# ADCS_Motherboard.net
KiCad netlist of a schematic drawn in EAGLE
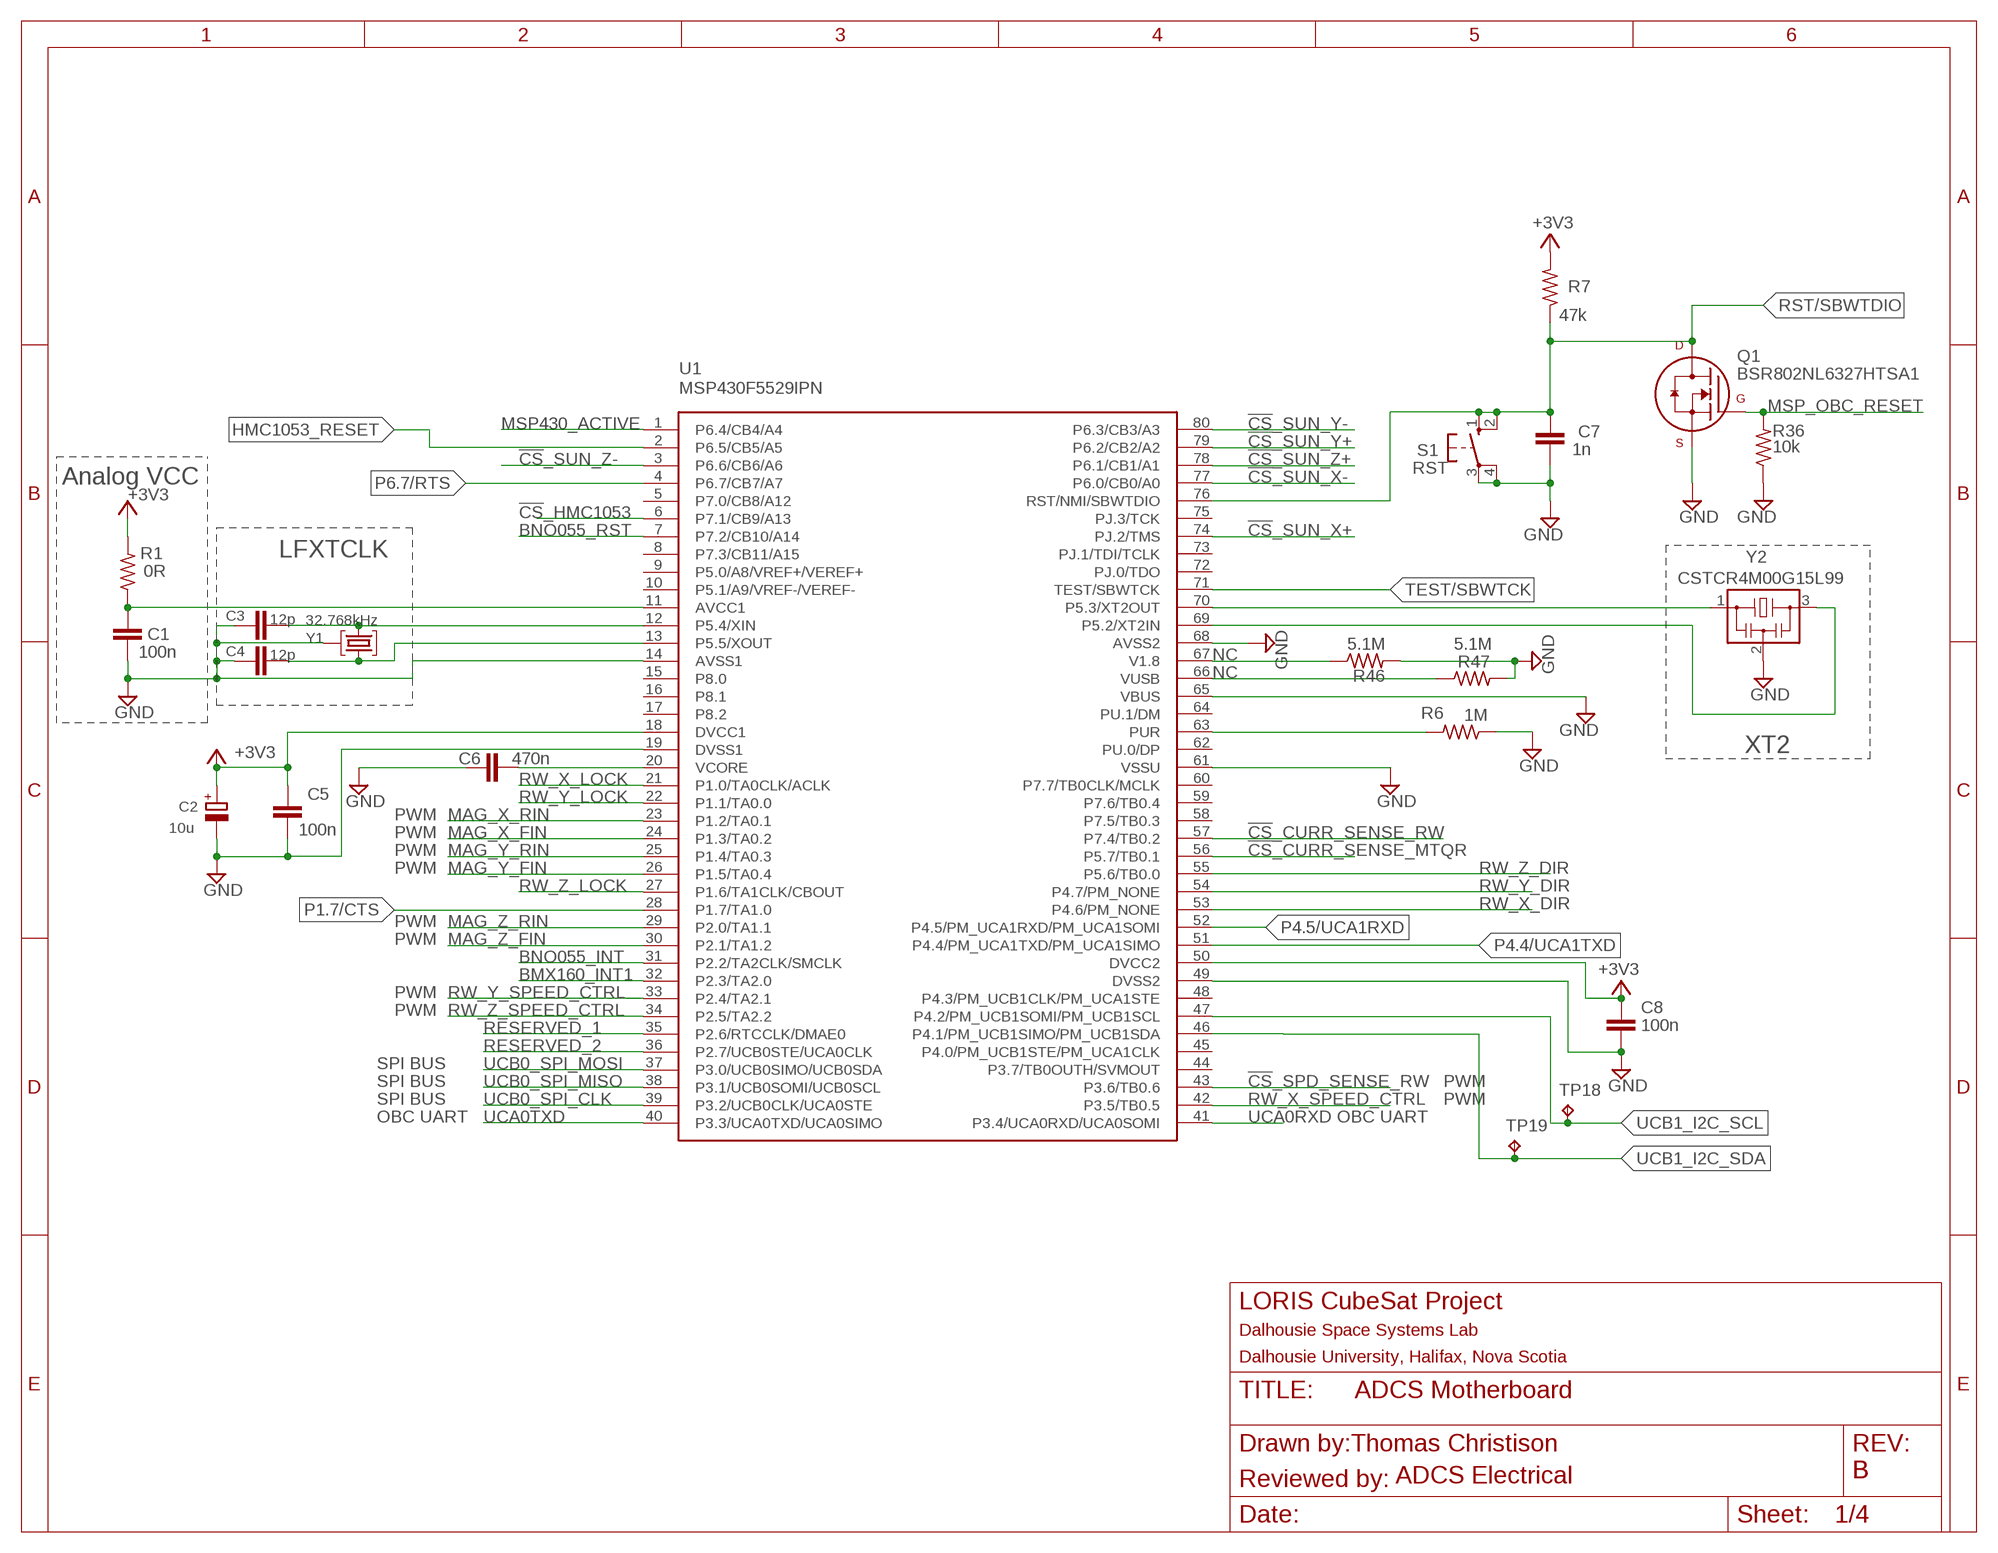
[diagram p0: schematic, sheet 1]
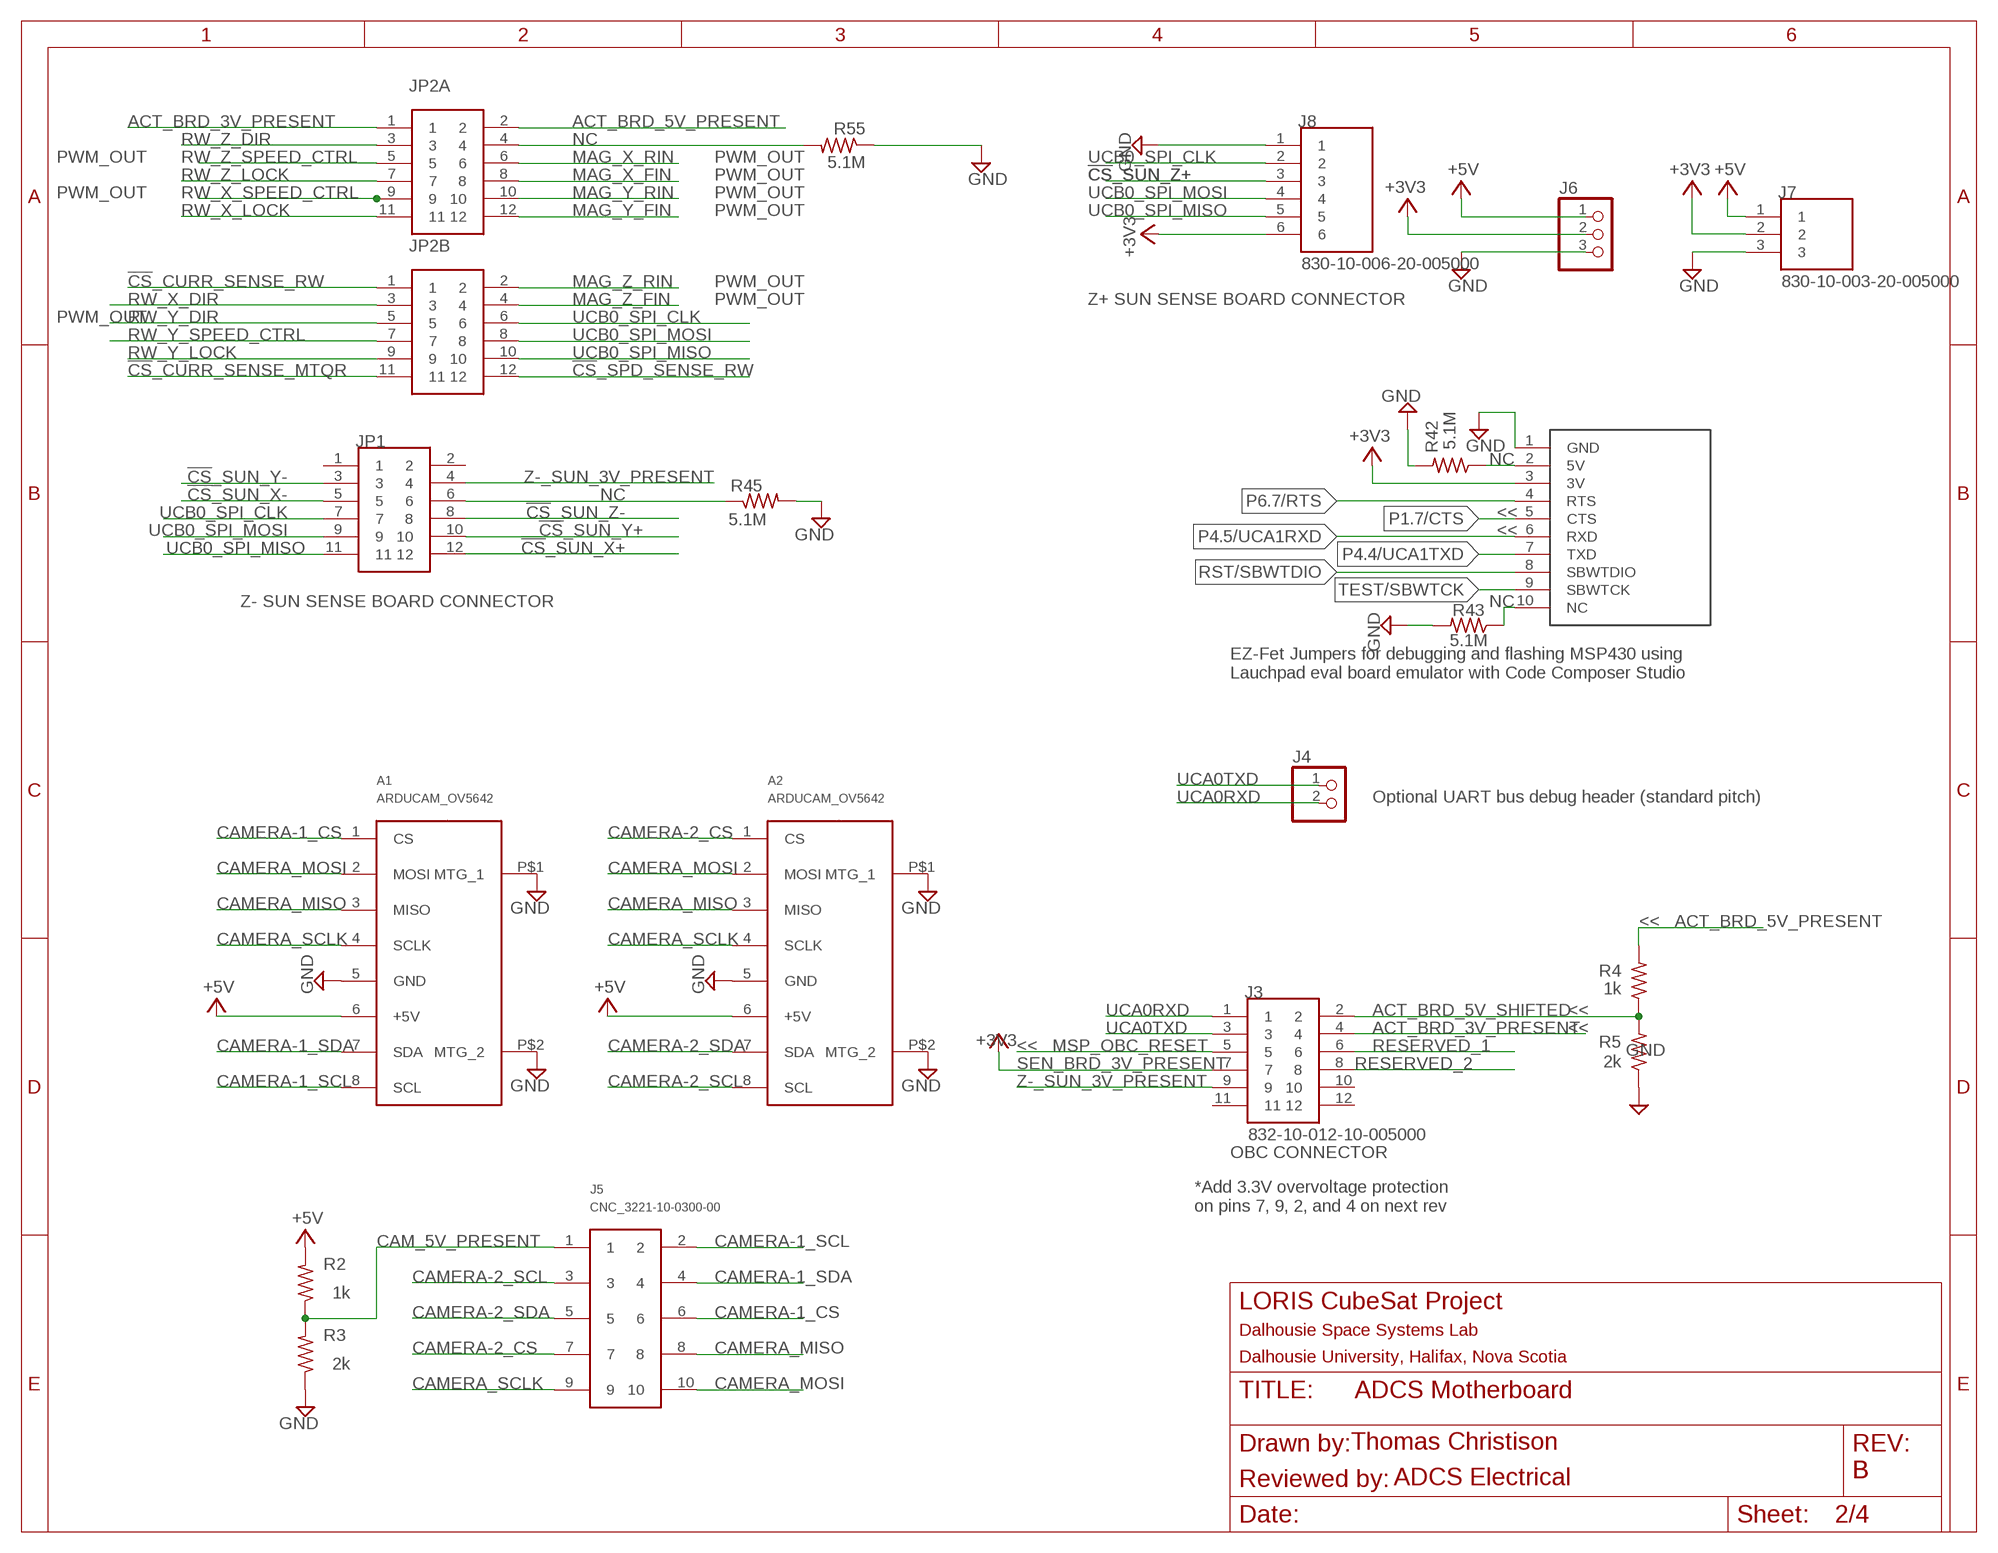
[diagram p1: schematic, sheet 2]
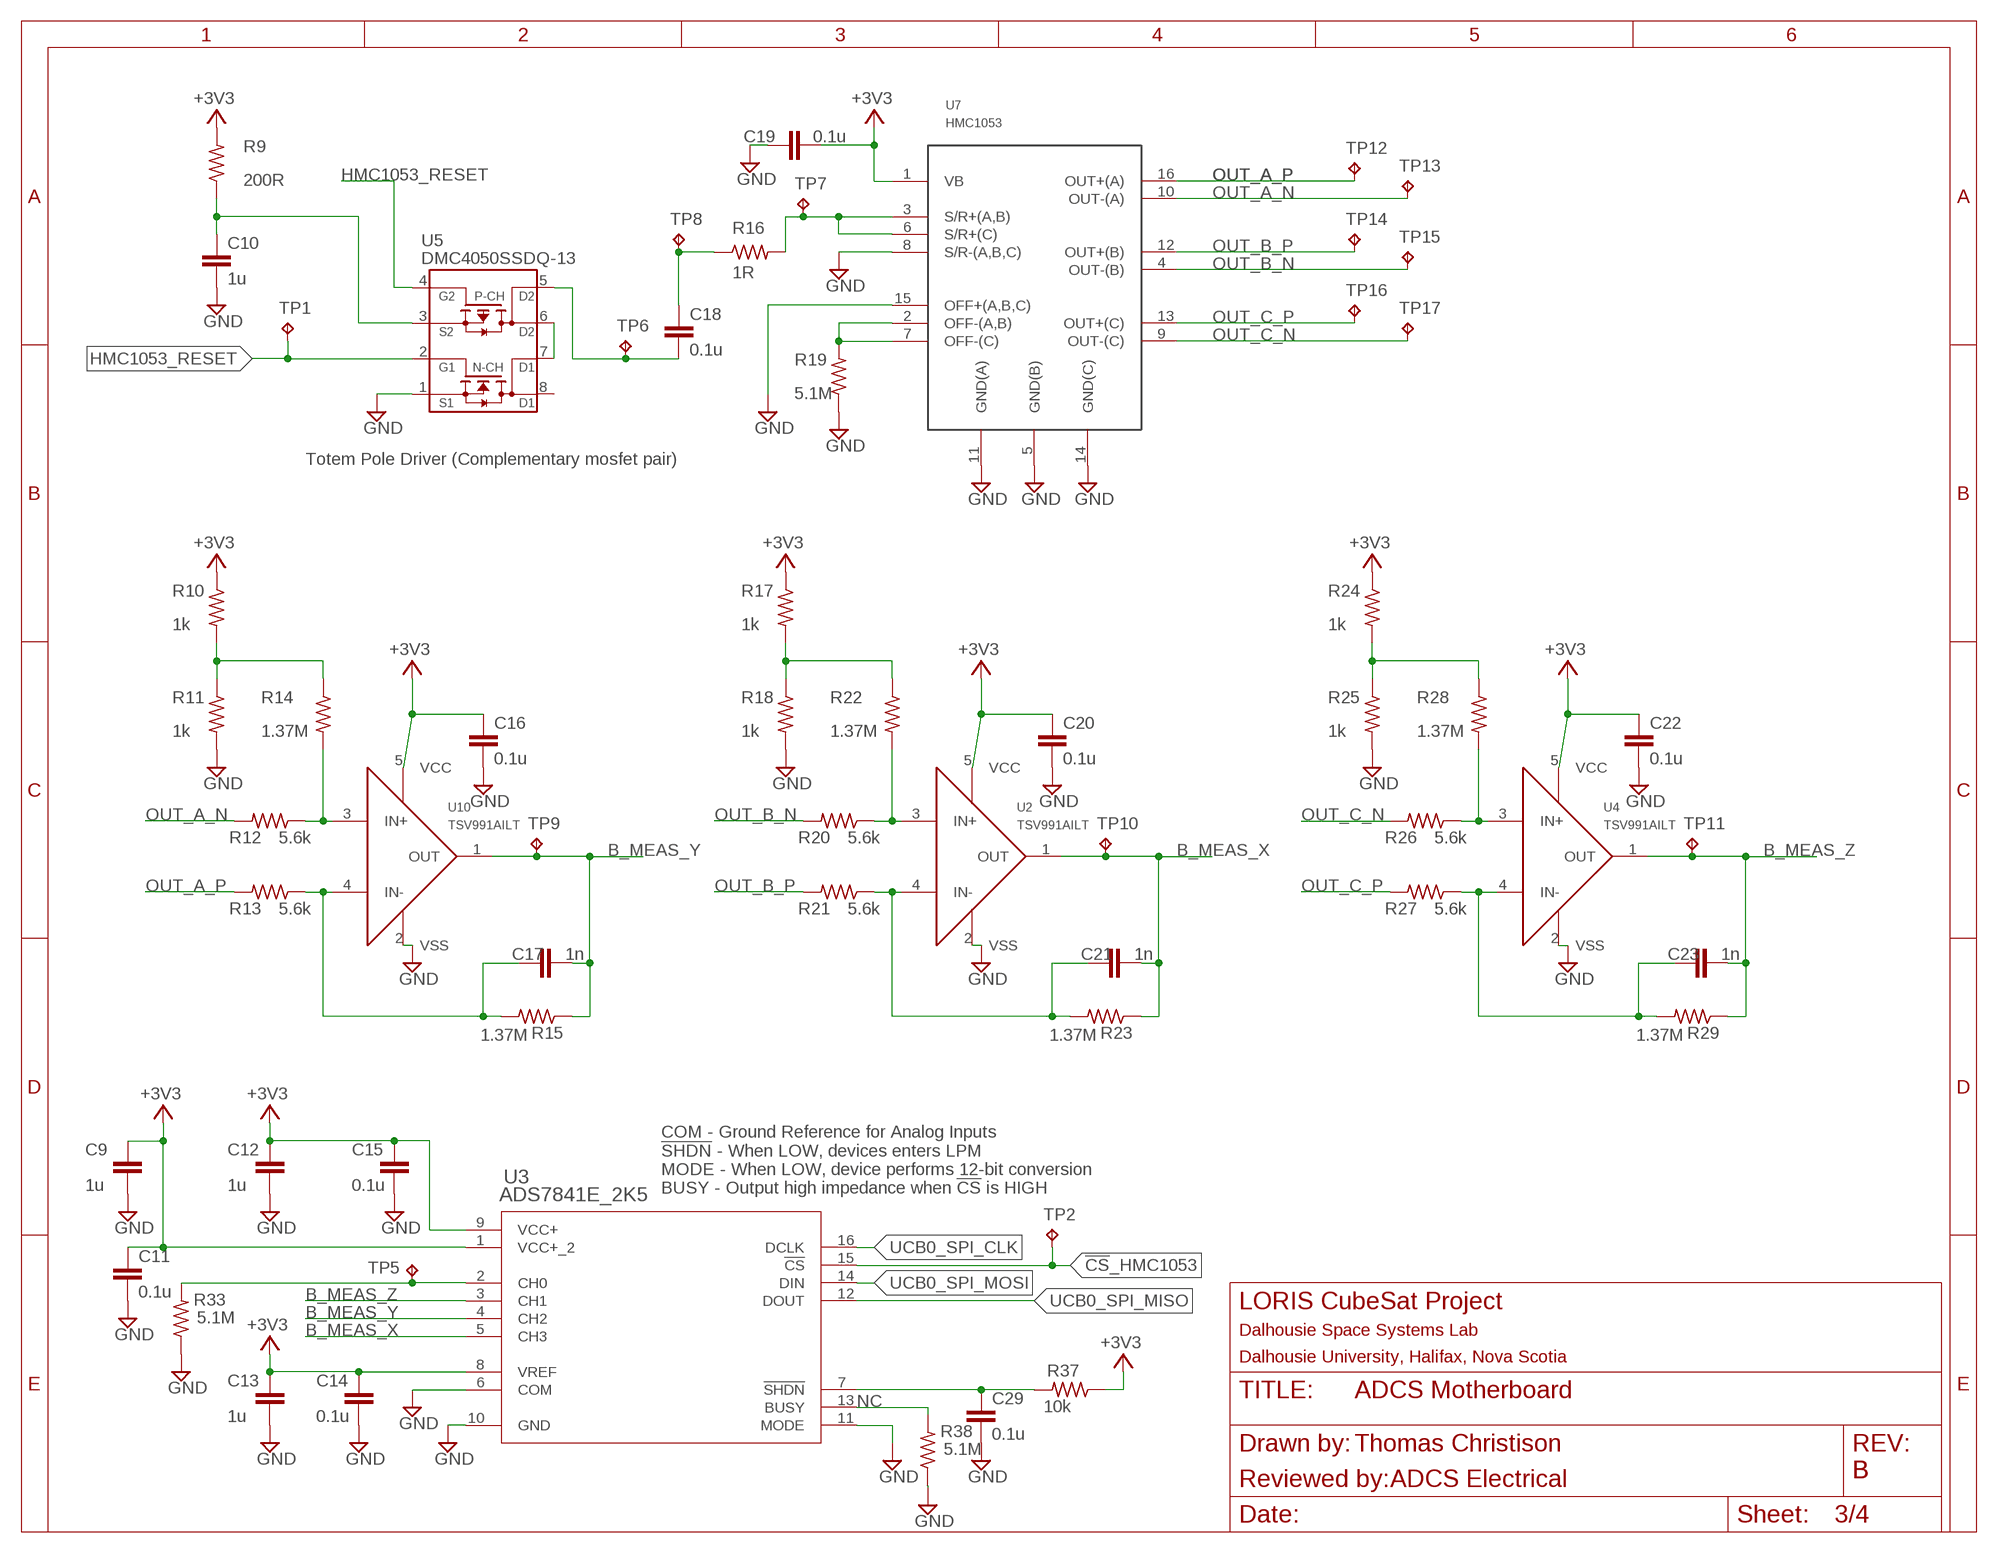
[diagram p2: schematic, sheet 3]
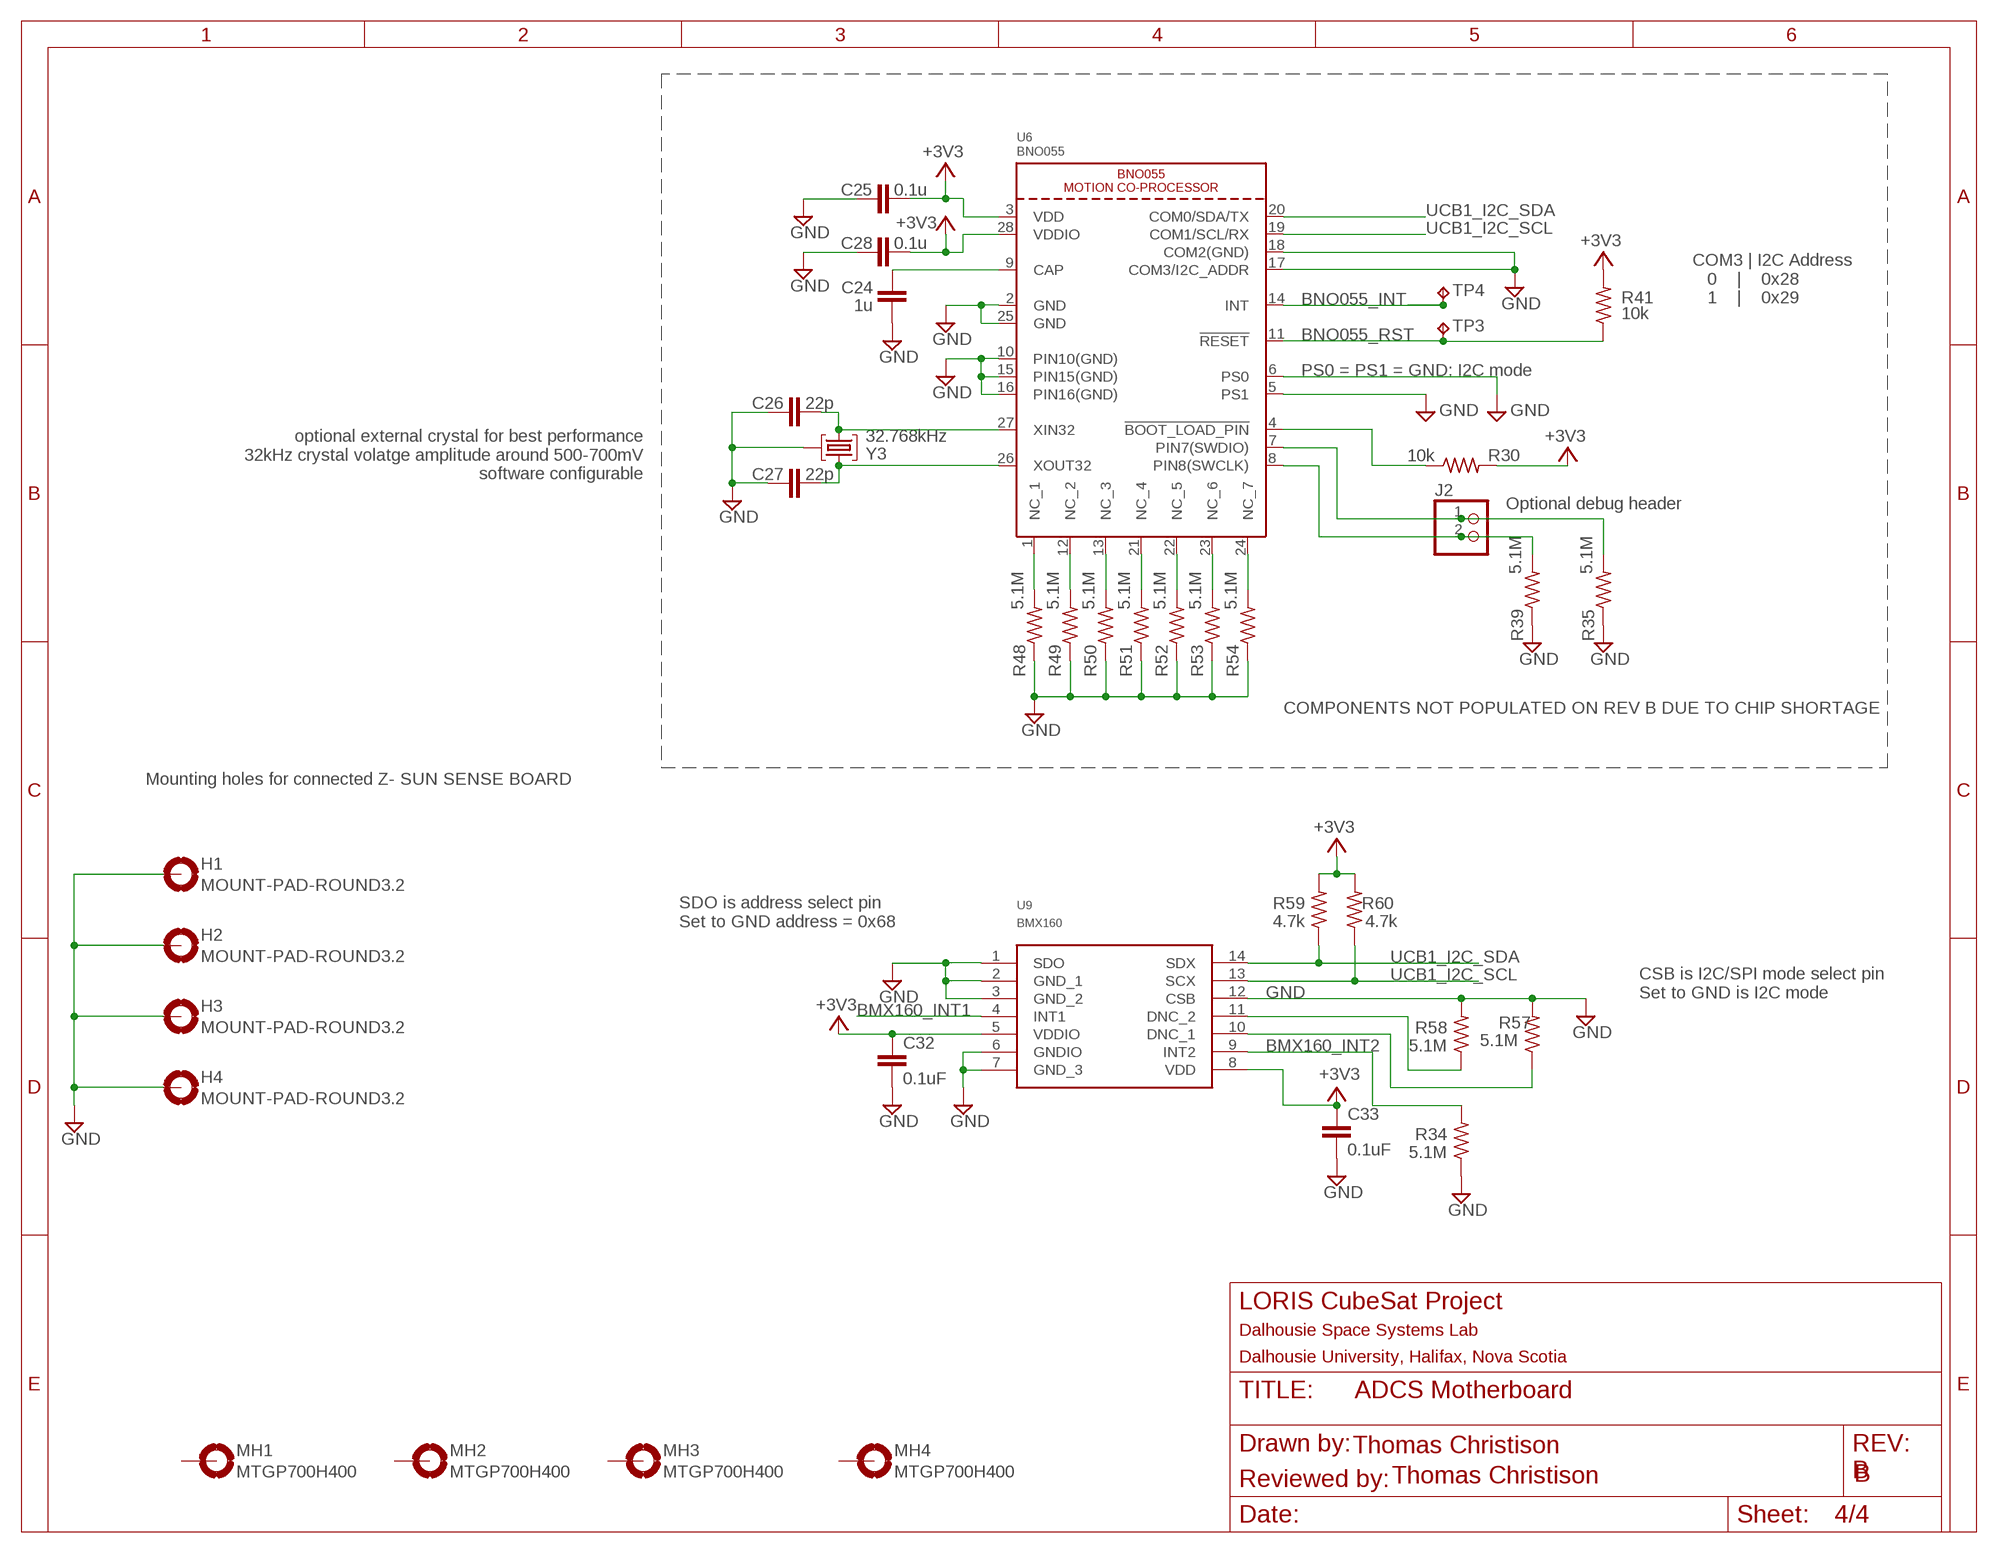
[diagram p3: schematic, sheet 4]

(export (version "E")
  (design (tool "Eeschema 10.0.6"))
  (components
    (comp (ref "C9")
      (value "1u")
      (footprint "eagle-import:C0805")
      (libsource (lib "eagle-import") (part "C-EUC0805"))
    )
    (comp (ref "C10")
      (value "1u")
      (footprint "eagle-import:C0603")
      (libsource (lib "eagle-import") (part "C-EUC0603"))
    )
    (comp (ref "C11")
      (value "0.1u")
      (footprint "eagle-import:C0603")
      (libsource (lib "eagle-import") (part "C-EUC0603"))
    )
    (comp (ref "C12")
      (value "1u")
      (footprint "eagle-import:C0805")
      (libsource (lib "eagle-import") (part "C-EUC0805"))
    )
    (comp (ref "C13")
      (value "1u")
      (footprint "eagle-import:C0805")
      (libsource (lib "eagle-import") (part "C-EUC0805"))
    )
    (comp (ref "C14")
      (value "0.1u")
      (footprint "eagle-import:C0603")
      (libsource (lib "eagle-import") (part "C-EUC0603"))
    )
    (comp (ref "C15")
      (value "0.1u")
      (footprint "eagle-import:C0603")
      (libsource (lib "eagle-import") (part "C-EUC0603"))
    )
    (comp (ref "C16")
      (value "0.1u")
      (footprint "eagle-import:C0603")
      (libsource (lib "eagle-import") (part "C-EUC0603"))
    )
    (comp (ref "C17")
      (value "1n")
      (footprint "eagle-import:C0603")
      (libsource (lib "eagle-import") (part "C-EUC0603"))
    )
    (comp (ref "C18")
      (value "0.1u")
      (footprint "eagle-import:C0805")
      (libsource (lib "eagle-import") (part "C-EUC0805"))
    )
    (comp (ref "C19")
      (value "0.1u")
      (footprint "eagle-import:C0603")
      (libsource (lib "eagle-import") (part "C-EUC0603"))
    )
    (comp (ref "C20")
      (value "0.1u")
      (footprint "eagle-import:C0603")
      (libsource (lib "eagle-import") (part "C-EUC0603"))
    )
    (comp (ref "C21")
      (value "1n")
      (footprint "eagle-import:C0603")
      (libsource (lib "eagle-import") (part "C-EUC0603"))
    )
    (comp (ref "C22")
      (value "0.1u")
      (footprint "eagle-import:C0603")
      (libsource (lib "eagle-import") (part "C-EUC0603"))
    )
    (comp (ref "C23")
      (value "1n")
      (footprint "eagle-import:C0603")
      (libsource (lib "eagle-import") (part "C-EUC0603"))
    )
    (comp (ref "C29")
      (value "0.1u")
      (footprint "eagle-import:C0603")
      (libsource (lib "eagle-import") (part "C-EUC0603"))
    )
    (comp (ref "R9")
      (value "200R")
      (footprint "eagle-import:R0805")
      (libsource (lib "eagle-import") (part "R-US_R0805"))
    )
    (comp (ref "R10")
      (value "1k")
      (footprint "eagle-import:R0603")
      (libsource (lib "eagle-import") (part "R-US_R0603"))
    )
    (comp (ref "R11")
      (value "1k")
      (footprint "eagle-import:R0603")
      (libsource (lib "eagle-import") (part "R-US_R0603"))
    )
    (comp (ref "R12")
      (value "5.6k")
      (footprint "eagle-import:R0603")
      (libsource (lib "eagle-import") (part "R-US_R0603"))
    )
    (comp (ref "R13")
      (value "5.6k")
      (footprint "eagle-import:R0603")
      (libsource (lib "eagle-import") (part "R-US_R0603"))
    )
    (comp (ref "R14")
      (value "1.37M")
      (footprint "eagle-import:R0603")
      (libsource (lib "eagle-import") (part "R-US_R0603"))
    )
    (comp (ref "R15")
      (value "1.37M")
      (footprint "eagle-import:R0603")
      (libsource (lib "eagle-import") (part "R-US_R0603"))
    )
    (comp (ref "R16")
      (value "1R")
      (footprint "eagle-import:R0805")
      (libsource (lib "eagle-import") (part "R-US_R0805"))
    )
    (comp (ref "R17")
      (value "1k")
      (footprint "eagle-import:R0603")
      (libsource (lib "eagle-import") (part "R-US_R0603"))
    )
    (comp (ref "R18")
      (value "1k")
      (footprint "eagle-import:R0603")
      (libsource (lib "eagle-import") (part "R-US_R0603"))
    )
    (comp (ref "R19")
      (value "5.1M")
      (footprint "eagle-import:R0402")
      (libsource (lib "eagle-import") (part "R-US_R0402"))
    )
    (comp (ref "R20")
      (value "5.6k")
      (footprint "eagle-import:R0603")
      (libsource (lib "eagle-import") (part "R-US_R0603"))
    )
    (comp (ref "R21")
      (value "5.6k")
      (footprint "eagle-import:R0603")
      (libsource (lib "eagle-import") (part "R-US_R0603"))
    )
    (comp (ref "R22")
      (value "1.37M")
      (footprint "eagle-import:R0603")
      (libsource (lib "eagle-import") (part "R-US_R0603"))
    )
    (comp (ref "R23")
      (value "1.37M")
      (footprint "eagle-import:R0603")
      (libsource (lib "eagle-import") (part "R-US_R0603"))
    )
    (comp (ref "R24")
      (value "1k")
      (footprint "eagle-import:R0603")
      (libsource (lib "eagle-import") (part "R-US_R0603"))
    )
    (comp (ref "R25")
      (value "1k")
      (footprint "eagle-import:R0603")
      (libsource (lib "eagle-import") (part "R-US_R0603"))
    )
    (comp (ref "R26")
      (value "5.6k")
      (footprint "eagle-import:R0603")
      (libsource (lib "eagle-import") (part "R-US_R0603"))
    )
    (comp (ref "R27")
      (value "5.6k")
      (footprint "eagle-import:R0603")
      (libsource (lib "eagle-import") (part "R-US_R0603"))
    )
    (comp (ref "R28")
      (value "1.37M")
      (footprint "eagle-import:R0603")
      (libsource (lib "eagle-import") (part "R-US_R0603"))
    )
    (comp (ref "R29")
      (value "1.37M")
      (footprint "eagle-import:R0603")
      (libsource (lib "eagle-import") (part "R-US_R0603"))
    )
    (comp (ref "R33")
      (value "5.1M")
      (footprint "eagle-import:R0402")
      (libsource (lib "eagle-import") (part "R-US_R0402"))
    )
    (comp (ref "R37")
      (value "10k")
      (footprint "eagle-import:R0603")
      (libsource (lib "eagle-import") (part "R-US_R0603"))
    )
    (comp (ref "R38")
      (value "5.1M")
      (footprint "eagle-import:R0402")
      (libsource (lib "eagle-import") (part "R-US_R0402"))
    )
    (comp (ref "TP1")
      (value "TESTPOINT")
      (footprint "eagle-import:TP_P76H50")
      (libsource (lib "eagle-import") (part "TESTPOINT"))
    )
    (comp (ref "TP2")
      (value "TESTPOINT")
      (footprint "eagle-import:TP_P76H50")
      (libsource (lib "eagle-import") (part "TESTPOINT"))
    )
    (comp (ref "TP5")
      (value "TESTPOINT")
      (footprint "eagle-import:TP_P76H50")
      (libsource (lib "eagle-import") (part "TESTPOINT"))
    )
    (comp (ref "TP6")
      (value "TESTPOINT")
      (footprint "eagle-import:TP_P76H50")
      (libsource (lib "eagle-import") (part "TESTPOINT"))
    )
    (comp (ref "TP7")
      (value "TESTPOINT")
      (footprint "eagle-import:TP_P76H50")
      (libsource (lib "eagle-import") (part "TESTPOINT"))
    )
    (comp (ref "TP8")
      (value "TESTPOINT")
      (footprint "eagle-import:TP_P76H50")
      (libsource (lib "eagle-import") (part "TESTPOINT"))
    )
    (comp (ref "TP9")
      (value "TESTPOINT")
      (footprint "eagle-import:TP_P76H50")
      (libsource (lib "eagle-import") (part "TESTPOINT"))
    )
    (comp (ref "TP10")
      (value "TESTPOINT")
      (footprint "eagle-import:TP_P76H50")
      (libsource (lib "eagle-import") (part "TESTPOINT"))
    )
    (comp (ref "TP11")
      (value "TESTPOINT")
      (footprint "eagle-import:TP_P76H50")
      (libsource (lib "eagle-import") (part "TESTPOINT"))
    )
    (comp (ref "TP12")
      (value "TESTPOINT")
      (footprint "eagle-import:TP_P76H50")
      (libsource (lib "eagle-import") (part "TESTPOINT"))
    )
    (comp (ref "TP13")
      (value "TESTPOINT")
      (footprint "eagle-import:TP_P76H50")
      (libsource (lib "eagle-import") (part "TESTPOINT"))
    )
    (comp (ref "TP14")
      (value "TESTPOINT")
      (footprint "eagle-import:TP_P76H50")
      (libsource (lib "eagle-import") (part "TESTPOINT"))
    )
    (comp (ref "TP15")
      (value "TESTPOINT")
      (footprint "eagle-import:TP_P76H50")
      (libsource (lib "eagle-import") (part "TESTPOINT"))
    )
    (comp (ref "TP16")
      (value "TESTPOINT")
      (footprint "eagle-import:TP_P76H50")
      (libsource (lib "eagle-import") (part "TESTPOINT"))
    )
    (comp (ref "TP17")
      (value "TESTPOINT")
      (footprint "eagle-import:TP_P76H50")
      (libsource (lib "eagle-import") (part "TESTPOINT"))
    )
    (comp (ref "U2")
      (value "TSV991AILT")
      (footprint "eagle-import:SOT95P280X145-5N")
      (libsource (lib "eagle-import") (part "TSV991AILT"))
    )
    (comp (ref "U3")
      (value "ADS7841E_2K5")
      (footprint "eagle-import:DBQ16")
      (fields
        (field (name "GENERIC_PART_NUMBER") "ADS7841")
        (field (name "MANUFACTURER") "Texas Instruments")
      )
      (libsource (lib "eagle-import") (part "ADS7841E_2K5"))
    )
    (comp (ref "U4")
      (value "TSV991AILT")
      (footprint "eagle-import:SOT95P280X145-5N")
      (libsource (lib "eagle-import") (part "TSV991AILT"))
    )
    (comp (ref "U5")
      (value "DMC4050SSDQ-13")
      (footprint "eagle-import:SOIC8P127_490X600X175L72X40N_DMC4050SSDQ-13")
      (libsource (lib "eagle-import") (part "DMC4050SSDQ-13"))
    )
    (comp (ref "U7")
      (value "HMC1053")
      (footprint "eagle-import:LCCS16P127_736X736X279L127X50N")
      (libsource (lib "eagle-import") (part "HMC1053"))
    )
    (comp (ref "U10")
      (value "TSV991AILT")
      (footprint "eagle-import:SOT95P280X145-5N")
      (libsource (lib "eagle-import") (part "TSV991AILT"))
    )
    (comp (ref "C1")
      (value "100n")
      (footprint "eagle-import:C0402")
      (libsource (lib "eagle-import") (part "C-EUC0402"))
    )
    (comp (ref "C2")
      (value "10u")
      (footprint "eagle-import:A_3216-18R")
      (libsource (lib "eagle-import") (part "POLARIZED_CAP"))
    )
    (comp (ref "C3")
      (value "12p")
      (footprint "eagle-import:C0402")
      (libsource (lib "eagle-import") (part "C-EUC0402"))
    )
    (comp (ref "C4")
      (value "12p")
      (footprint "eagle-import:C0402")
      (libsource (lib "eagle-import") (part "C-EUC0402"))
    )
    (comp (ref "C5")
      (value "100n")
      (footprint "eagle-import:C0402")
      (libsource (lib "eagle-import") (part "C-EUC0402"))
    )
    (comp (ref "C6")
      (value "470n")
      (footprint "eagle-import:C0402")
      (libsource (lib "eagle-import") (part "C-EUC0402"))
    )
    (comp (ref "C7")
      (value "1n")
      (footprint "eagle-import:C0402")
      (libsource (lib "eagle-import") (part "C-EUC0402"))
    )
    (comp (ref "C8")
      (value "100n")
      (footprint "eagle-import:C0402")
      (libsource (lib "eagle-import") (part "C-EUC0402"))
    )
    (comp (ref "Q1")
      (value "BSR802NL6327HTSA1")
      (footprint "eagle-import:SOT23-3P95_230X110L20X43N_PMV16XN")
      (libsource (lib "eagle-import") (part "BSR802NL6327HTSA1"))
    )
    (comp (ref "R1")
      (value "0R")
      (footprint "eagle-import:R0402")
      (libsource (lib "eagle-import") (part "R-US_R0402"))
    )
    (comp (ref "R6")
      (value "1M")
      (footprint "eagle-import:R0603")
      (libsource (lib "eagle-import") (part "R-US_R0603"))
    )
    (comp (ref "R7")
      (value "47k")
      (footprint "eagle-import:R0402")
      (libsource (lib "eagle-import") (part "R-US_R0402"))
    )
    (comp (ref "R36")
      (value "10k")
      (footprint "eagle-import:R0603")
      (libsource (lib "eagle-import") (part "R-US_R0603"))
    )
    (comp (ref "R46")
      (value "5.1M")
      (footprint "eagle-import:R0402")
      (libsource (lib "eagle-import") (part "R-US_R0402"))
    )
    (comp (ref "R47")
      (value "5.1M")
      (footprint "eagle-import:R0402")
      (libsource (lib "eagle-import") (part "R-US_R0402"))
    )
    (comp (ref "S1")
      (value "RST")
      (footprint "eagle-import:B3F-10XX")
      (fields (field (name "MPN") "B3F-1000"))
      (libsource (lib "eagle-import") (part "10-XX"))
    )
    (comp (ref "TP18")
      (value "TESTPOINT")
      (footprint "eagle-import:TP_P76H50")
      (libsource (lib "eagle-import") (part "TESTPOINT"))
    )
    (comp (ref "TP19")
      (value "TESTPOINT")
      (footprint "eagle-import:TP_P76H50")
      (libsource (lib "eagle-import") (part "TESTPOINT"))
    )
    (comp (ref "U1")
      (value "MSP430F5529IPN")
      (footprint "eagle-import:QFP80P50_1400X1400X160L60X22N")
      (libsource (lib "eagle-import") (part "MSP430F5529IPN"))
    )
    (comp (ref "Y1")
      (value "32.768kHz")
      (footprint "eagle-import:MS3V-T1R")
      (libsource (lib "eagle-import") (part "MS3V-T1R"))
    )
    (comp (ref "Y2")
      (value "CSTCR4M00G15L99")
      (footprint "eagle-import:MURATA-FILTER_CSTCR")
      (fields (field (name "MPN") "CSTCR6M00G53-R0"))
      (libsource (lib "eagle-import") (part "CSTCR4M00G15L996M00G53Z"))
    )
    (comp (ref "C24")
      (value "1u")
      (footprint "eagle-import:C0402")
      (libsource (lib "eagle-import") (part "C-EUC0402"))
    )
    (comp (ref "C25")
      (value "0.1u")
      (footprint "eagle-import:C0402")
      (libsource (lib "eagle-import") (part "C-EUC0402"))
    )
    (comp (ref "C26")
      (value "22p")
      (footprint "eagle-import:C0402")
      (libsource (lib "eagle-import") (part "C-EUC0402"))
    )
    (comp (ref "C27")
      (value "22p")
      (footprint "eagle-import:C0402")
      (libsource (lib "eagle-import") (part "C-EUC0402"))
    )
    (comp (ref "C28")
      (value "0.1u")
      (footprint "eagle-import:C0402")
      (libsource (lib "eagle-import") (part "C-EUC0402"))
    )
    (comp (ref "C32")
      (value "0.1uF")
      (footprint "eagle-import:C0805")
      (libsource (lib "eagle-import") (part "C-EUC0805"))
    )
    (comp (ref "C33")
      (value "0.1uF")
      (footprint "eagle-import:C0805")
      (libsource (lib "eagle-import") (part "C-EUC0805"))
    )
    (comp (ref "H1")
      (value "MOUNT-PAD-ROUND3.2")
      (footprint "eagle-import:3,2-PAD")
      (libsource (lib "eagle-import") (part "MOUNT-PAD-ROUND3.2"))
    )
    (comp (ref "H2")
      (value "MOUNT-PAD-ROUND3.2")
      (footprint "eagle-import:3,2-PAD")
      (libsource (lib "eagle-import") (part "MOUNT-PAD-ROUND3.2"))
    )
    (comp (ref "H3")
      (value "MOUNT-PAD-ROUND3.2")
      (footprint "eagle-import:3,2-PAD")
      (libsource (lib "eagle-import") (part "MOUNT-PAD-ROUND3.2"))
    )
    (comp (ref "H4")
      (value "MOUNT-PAD-ROUND3.2")
      (footprint "eagle-import:3,2-PAD")
      (libsource (lib "eagle-import") (part "MOUNT-PAD-ROUND3.2"))
    )
    (comp (ref "J2")
      (value "HDR_1X2_")
      (footprint "eagle-import:1X02")
      (libsource (lib "eagle-import") (part "HDR_1X2_"))
    )
    (comp (ref "MH1")
      (value "MTGP700H400")
      (footprint "eagle-import:MTGP700H400")
      (libsource (lib "eagle-import") (part "MTGP700H400"))
    )
    (comp (ref "MH2")
      (value "MTGP700H400")
      (footprint "eagle-import:MTGP700H400")
      (libsource (lib "eagle-import") (part "MTGP700H400"))
    )
    (comp (ref "MH3")
      (value "MTGP700H400")
      (footprint "eagle-import:MTGP700H400")
      (libsource (lib "eagle-import") (part "MTGP700H400"))
    )
    (comp (ref "MH4")
      (value "MTGP700H400")
      (footprint "eagle-import:MTGP700H400")
      (libsource (lib "eagle-import") (part "MTGP700H400"))
    )
    (comp (ref "R30")
      (value "10k")
      (footprint "eagle-import:R0402")
      (libsource (lib "eagle-import") (part "R-US_R0402"))
    )
    (comp (ref "R34")
      (value "5.1M")
      (footprint "eagle-import:R0402")
      (libsource (lib "eagle-import") (part "R-US_R0402"))
    )
    (comp (ref "R35")
      (value "5.1M")
      (footprint "eagle-import:R0402")
      (libsource (lib "eagle-import") (part "R-US_R0402"))
    )
    (comp (ref "R39")
      (value "5.1M")
      (footprint "eagle-import:R0402")
      (libsource (lib "eagle-import") (part "R-US_R0402"))
    )
    (comp (ref "R41")
      (value "10k")
      (footprint "eagle-import:R0402")
      (libsource (lib "eagle-import") (part "R-US_R0402"))
    )
    (comp (ref "R48")
      (value "5.1M")
      (footprint "eagle-import:R0402")
      (libsource (lib "eagle-import") (part "R-US_R0402"))
    )
    (comp (ref "R49")
      (value "5.1M")
      (footprint "eagle-import:R0402")
      (libsource (lib "eagle-import") (part "R-US_R0402"))
    )
    (comp (ref "R50")
      (value "5.1M")
      (footprint "eagle-import:R0402")
      (libsource (lib "eagle-import") (part "R-US_R0402"))
    )
    (comp (ref "R51")
      (value "5.1M")
      (footprint "eagle-import:R0402")
      (libsource (lib "eagle-import") (part "R-US_R0402"))
    )
    (comp (ref "R52")
      (value "5.1M")
      (footprint "eagle-import:R0402")
      (libsource (lib "eagle-import") (part "R-US_R0402"))
    )
    (comp (ref "R53")
      (value "5.1M")
      (footprint "eagle-import:R0402")
      (libsource (lib "eagle-import") (part "R-US_R0402"))
    )
    (comp (ref "R54")
      (value "5.1M")
      (footprint "eagle-import:R0402")
      (libsource (lib "eagle-import") (part "R-US_R0402"))
    )
    (comp (ref "R57")
      (value "5.1M")
      (footprint "eagle-import:R0402")
      (libsource (lib "eagle-import") (part "R-US_R0402"))
    )
    (comp (ref "R58")
      (value "5.1M")
      (footprint "eagle-import:R0402")
      (libsource (lib "eagle-import") (part "R-US_R0402"))
    )
    (comp (ref "R59")
      (value "4.7k")
      (footprint "eagle-import:R0603")
      (libsource (lib "eagle-import") (part "R-US_R0603"))
    )
    (comp (ref "R60")
      (value "4.7k")
      (footprint "eagle-import:R0603")
      (libsource (lib "eagle-import") (part "R-US_R0603"))
    )
    (comp (ref "TP3")
      (value "TESTPOINT")
      (footprint "eagle-import:TP_P76H50")
      (libsource (lib "eagle-import") (part "TESTPOINT"))
    )
    (comp (ref "TP4")
      (value "TESTPOINT")
      (footprint "eagle-import:TP_P76H50")
      (libsource (lib "eagle-import") (part "TESTPOINT"))
    )
    (comp (ref "U6")
      (value "BNO055")
      (footprint "eagle-import:BNO055")
      (libsource (lib "eagle-import") (part "BNO055"))
    )
    (comp (ref "U9")
      (value "BMX160")
      (footprint "eagle-import:QFN14P50_300X250X100L47X25N")
      (libsource (lib "eagle-import") (part "BMX160"))
    )
    (comp (ref "Y3")
      (value "32.768kHz")
      (footprint "eagle-import:MS3V-T1R")
      (libsource (lib "eagle-import") (part "MS3V-T1R"))
    )
    (comp (ref "A1")
      (value "ARDUCAM_OV5642")
      (footprint "eagle-import:ARDUCAM")
      (libsource (lib "eagle-import") (part "ARDUCAM_OV5642"))
    )
    (comp (ref "A2")
      (value "ARDUCAM_OV5642")
      (footprint "eagle-import:ARDUCAM")
      (libsource (lib "eagle-import") (part "ARDUCAM_OV5642"))
    )
    (comp (ref "J1")
      (value "HDR_10_EZFET_DEBUGGER")
      (footprint "eagle-import:HDRV10W66P254_10X1_2540X254H858")
      (libsource (lib "eagle-import") (part "HDR_10_EZFET_DEBUGGER"))
    )
    (comp (ref "J3")
      (value "832-10-012-10-005000")
      (footprint "eagle-import:832-10-012-10-005000")
      (fields (field (name "COMMENT") "2355104-4") (field (name "MF") "TE Connectivity"))
      (libsource (lib "eagle-import") (part "832-10-012-10-005000"))
    )
    (comp (ref "J4")
      (value "HDR_1X2_")
      (footprint "eagle-import:1X02")
      (libsource (lib "eagle-import") (part "HDR_1X2_"))
    )
    (comp (ref "J5")
      (value "CNC_3221-10-0300-00")
      (footprint "eagle-import:CNC_3221-10-0300-00")
      (libsource (lib "eagle-import") (part "CNC_3221-10-0300-00"))
    )
    (comp (ref "J6")
      (value "PINHD-1X3")
      (footprint "eagle-import:1X03")
      (libsource (lib "eagle-import") (part "PINHD-1X3"))
    )
    (comp (ref "J7")
      (value "830-10-003-20-005000")
      (footprint "eagle-import:830-10-003-20-005000")
      (fields (field (name "COMMENT") "2355104-4") (field (name "MF") "TE Connectivity"))
      (libsource (lib "eagle-import") (part "830-10-003-20-005000"))
    )
    (comp (ref "J8")
      (value "830-10-006-20-005000")
      (footprint "eagle-import:830-10-006-20-005000")
      (fields (field (name "COMMENT") "2355104-4") (field (name "MF") "TE Connectivity"))
      (libsource (lib "eagle-import") (part "830-10-006-20-005000"))
    )
    (comp (ref "JP1")
      (value "832-10-012-10-005000")
      (footprint "eagle-import:832-10-012-10-005000")
      (fields (field (name "COMMENT") "2355104-4") (field (name "MF") "TE Connectivity"))
      (libsource (lib "eagle-import") (part "832-10-012-10-005000"))
    )
    (comp (ref "JP2A")
      (value "832-10-012-10-005000")
      (footprint "eagle-import:832-10-012-10-005000")
      (fields (field (name "COMMENT") "2355104-4") (field (name "MF") "TE Connectivity"))
      (libsource (lib "eagle-import") (part "832-10-012-10-005000"))
    )
    (comp (ref "JP2B")
      (value "832-10-012-10-005000")
      (footprint "eagle-import:832-10-012-10-005000")
      (fields (field (name "COMMENT") "2355104-4") (field (name "MF") "TE Connectivity"))
      (libsource (lib "eagle-import") (part "832-10-012-10-005000"))
    )
    (comp (ref "R2")
      (value "1k")
      (footprint "eagle-import:R0603")
      (libsource (lib "eagle-import") (part "R-US_R0603"))
    )
    (comp (ref "R3")
      (value "2k")
      (footprint "eagle-import:R0603")
      (libsource (lib "eagle-import") (part "R-US_R0603"))
    )
    (comp (ref "R4")
      (value "1k")
      (footprint "eagle-import:R0603")
      (libsource (lib "eagle-import") (part "R-US_R0603"))
    )
    (comp (ref "R5")
      (value "2k")
      (footprint "eagle-import:R0603")
      (libsource (lib "eagle-import") (part "R-US_R0603"))
    )
    (comp (ref "R42")
      (value "5.1M")
      (footprint "eagle-import:R0402")
      (libsource (lib "eagle-import") (part "R-US_R0402"))
    )
    (comp (ref "R43")
      (value "5.1M")
      (footprint "eagle-import:R0402")
      (libsource (lib "eagle-import") (part "R-US_R0402"))
    )
    (comp (ref "R45")
      (value "5.1M")
      (footprint "eagle-import:R0402")
      (libsource (lib "eagle-import") (part "R-US_R0402"))
    )
    (comp (ref "R55")
      (value "5.1M")
      (footprint "eagle-import:R0402")
      (libsource (lib "eagle-import") (part "R-US_R0402"))
    )
  )
  (nets
    (net (code "1") (name "+3V3") (class "Default")
      (node (ref "C11") (pin "1") (pinfunction "1_1") (pintype "passive"))
      (node (ref "C12") (pin "1") (pinfunction "1_1") (pintype "passive"))
      (node (ref "C13") (pin "1") (pinfunction "1_1") (pintype "passive"))
      (node (ref "C14") (pin "1") (pinfunction "1_1") (pintype "passive"))
      (node (ref "C15") (pin "1") (pinfunction "1_1") (pintype "passive"))
      (node (ref "C16") (pin "1") (pinfunction "1_1") (pintype "passive"))
      (node (ref "C19") (pin "1") (pinfunction "1_1") (pintype "passive"))
      (node (ref "C2") (pin "+") (pinfunction "+_+") (pintype "passive"))
      (node (ref "C20") (pin "1") (pinfunction "1_1") (pintype "passive"))
      (node (ref "C22") (pin "1") (pinfunction "1_1") (pintype "passive"))
      (node (ref "C25") (pin "2") (pinfunction "2_2") (pintype "passive"))
      (node (ref "C28") (pin "2") (pinfunction "2_2") (pintype "passive"))
      (node (ref "C32") (pin "1") (pinfunction "1_1") (pintype "passive"))
      (node (ref "C33") (pin "1") (pinfunction "1_1") (pintype "passive"))
      (node (ref "C5") (pin "2") (pinfunction "2_2") (pintype "passive"))
      (node (ref "C8") (pin "1") (pinfunction "1_1") (pintype "passive"))
      (node (ref "C9") (pin "1") (pinfunction "1_1") (pintype "passive"))
      (node (ref "J1") (pin "3") (pinfunction "3V_3") (pintype "bidirectional"))
      (node (ref "J3") (pin "7") (pinfunction "7_7") (pintype "passive"))
      (node (ref "J6") (pin "2") (pinfunction "2_2") (pintype "passive"))
      (node (ref "J7") (pin "2") (pinfunction "2_2") (pintype "passive"))
      (node (ref "J8") (pin "6") (pinfunction "6_6") (pintype "passive"))
      (node (ref "R1") (pin "2") (pinfunction "2_2") (pintype "passive"))
      (node (ref "R10") (pin "1") (pinfunction "1_1") (pintype "passive"))
      (node (ref "R17") (pin "1") (pinfunction "1_1") (pintype "passive"))
      (node (ref "R24") (pin "1") (pinfunction "1_1") (pintype "passive"))
      (node (ref "R30") (pin "2") (pinfunction "2_2") (pintype "passive"))
      (node (ref "R37") (pin "1") (pinfunction "1_1") (pintype "passive"))
      (node (ref "R41") (pin "2") (pinfunction "2_2") (pintype "passive"))
      (node (ref "R59") (pin "2") (pinfunction "2_2") (pintype "passive"))
      (node (ref "R60") (pin "2") (pinfunction "2_2") (pintype "passive"))
      (node (ref "R7") (pin "2") (pinfunction "2_2") (pintype "passive"))
      (node (ref "R9") (pin "2") (pinfunction "2_2") (pintype "passive"))
      (node (ref "U1") (pin "18") (pinfunction "DVCC1_18") (pintype "bidirectional"))
      (node (ref "U1") (pin "50") (pinfunction "DVCC2_50") (pintype "bidirectional"))
      (node (ref "U10") (pin "5") (pinfunction "VCC_5") (pintype "power_in"))
      (node (ref "U2") (pin "5") (pinfunction "VCC_5") (pintype "power_in"))
      (node (ref "U3") (pin "1") (pinfunction "VCC+_2_1") (pintype "power_in"))
      (node (ref "U3") (pin "8") (pinfunction "VREF_8") (pintype "input"))
      (node (ref "U3") (pin "9") (pinfunction "VCC+_9") (pintype "power_in"))
      (node (ref "U4") (pin "5") (pinfunction "VCC_5") (pintype "power_in"))
      (node (ref "U6") (pin "28") (pinfunction "VDDIO_28") (pintype "power_in"))
      (node (ref "U6") (pin "3") (pinfunction "VDD_3") (pintype "power_in"))
      (node (ref "U7") (pin "1") (pinfunction "VB_1") (pintype "bidirectional"))
      (node (ref "U9") (pin "5") (pinfunction "VDDIO_5") (pintype "bidirectional"))
      (node (ref "U9") (pin "8") (pinfunction "VDD_8") (pintype "bidirectional"))
    )
    (net (code "2") (name "+5V") (class "Default")
      (node (ref "A1") (pin "6") (pinfunction "+5V_6") (pintype "bidirectional"))
      (node (ref "A2") (pin "6") (pinfunction "+5V_6") (pintype "bidirectional"))
      (node (ref "J6") (pin "1") (pinfunction "1_1") (pintype "passive"))
      (node (ref "J7") (pin "1") (pinfunction "1_1") (pintype "passive"))
      (node (ref "R2") (pin "2") (pinfunction "2_2") (pintype "passive"))
    )
    (net (code "3") (name "ACT_BRD_3V_PRESENT") (class "Default")
      (node (ref "J3") (pin "4") (pinfunction "4_4") (pintype "passive"))
      (node (ref "JP2A") (pin "1") (pinfunction "1_1") (pintype "passive"))
    )
    (net (code "4") (name "ACT_BRD_5V_PRESENT") (class "Default")
      (node (ref "JP2A") (pin "2") (pinfunction "2_2") (pintype "passive"))
      (node (ref "R4") (pin "2") (pinfunction "2_2") (pintype "passive"))
    )
    (net (code "5") (name "ACT_BRD_5V_SHIFTED") (class "Default")
      (node (ref "J3") (pin "2") (pinfunction "2_2") (pintype "passive"))
      (node (ref "R4") (pin "1") (pinfunction "1_1") (pintype "passive"))
      (node (ref "R5") (pin "2") (pinfunction "2_2") (pintype "passive"))
    )
    (net (code "6") (name "BMX160_INT1") (class "Default")
      (node (ref "U1") (pin "32") (pinfunction "P2.3/TA2.0_32") (pintype "bidirectional"))
      (node (ref "U9") (pin "4") (pinfunction "INT1_4") (pintype "bidirectional"))
    )
    (net (code "7") (name "BMX160_INT2") (class "Default")
      (node (ref "R34") (pin "2") (pinfunction "2_2") (pintype "passive"))
      (node (ref "U9") (pin "9") (pinfunction "INT2_9") (pintype "bidirectional"))
    )
    (net (code "8") (name "BNO055_INT") (class "Default")
      (node (ref "TP4") (pin "1") (pinfunction "TP_1") (pintype "input"))
      (node (ref "U1") (pin "31") (pinfunction "P2.2/TA2CLK/SMCLK_31") (pintype "bidirectional"))
      (node (ref "U6") (pin "14") (pinfunction "INT_14") (pintype "output"))
    )
    (net (code "9") (name "BNO055_RST") (class "Default")
      (node (ref "R41") (pin "1") (pinfunction "1_1") (pintype "passive"))
      (node (ref "TP3") (pin "1") (pinfunction "TP_1") (pintype "input"))
      (node (ref "U1") (pin "7") (pinfunction "P7.2/CB10/A14_7") (pintype "bidirectional"))
      (node (ref "U6") (pin "11") (pinfunction "~{RESET}_11") (pintype "bidirectional"))
    )
    (net (code "10") (name "B_MEAS_X") (class "Default")
      (node (ref "C21") (pin "2") (pinfunction "2_2") (pintype "passive"))
      (node (ref "R23") (pin "1") (pinfunction "1_1") (pintype "passive"))
      (node (ref "TP10") (pin "1") (pinfunction "TP_1") (pintype "input"))
      (node (ref "U2") (pin "1") (pinfunction "OUT_1") (pintype "output"))
      (node (ref "U3") (pin "5") (pinfunction "CH3_5") (pintype "input"))
    )
    (net (code "11") (name "B_MEAS_Y") (class "Default")
      (node (ref "C17") (pin "2") (pinfunction "2_2") (pintype "passive"))
      (node (ref "R15") (pin "1") (pinfunction "1_1") (pintype "passive"))
      (node (ref "TP9") (pin "1") (pinfunction "TP_1") (pintype "input"))
      (node (ref "U10") (pin "1") (pinfunction "OUT_1") (pintype "output"))
      (node (ref "U3") (pin "4") (pinfunction "CH2_4") (pintype "input"))
    )
    (net (code "12") (name "B_MEAS_Z") (class "Default")
      (node (ref "C23") (pin "2") (pinfunction "2_2") (pintype "passive"))
      (node (ref "R29") (pin "1") (pinfunction "1_1") (pintype "passive"))
      (node (ref "TP11") (pin "1") (pinfunction "TP_1") (pintype "input"))
      (node (ref "U3") (pin "3") (pinfunction "CH1_3") (pintype "input"))
      (node (ref "U4") (pin "1") (pinfunction "OUT_1") (pintype "output"))
    )
    (net (code "13") (name "CAMERA-1_CS") (class "Default")
      (node (ref "A1") (pin "1") (pinfunction "CS_1") (pintype "bidirectional"))
      (node (ref "J5") (pin "6") (pinfunction "6_6") (pintype "bidirectional"))
    )
    (net (code "14") (name "CAMERA-1_SCL") (class "Default")
      (node (ref "A1") (pin "8") (pinfunction "SCL_8") (pintype "bidirectional"))
      (node (ref "J5") (pin "2") (pinfunction "2_2") (pintype "bidirectional"))
    )
    (net (code "15") (name "CAMERA-1_SDA") (class "Default")
      (node (ref "A1") (pin "7") (pinfunction "SDA_7") (pintype "bidirectional"))
      (node (ref "J5") (pin "4") (pinfunction "4_4") (pintype "bidirectional"))
    )
    (net (code "16") (name "CAMERA-2_CS") (class "Default")
      (node (ref "A2") (pin "1") (pinfunction "CS_1") (pintype "bidirectional"))
      (node (ref "J5") (pin "7") (pinfunction "7_7") (pintype "bidirectional"))
    )
    (net (code "17") (name "CAMERA-2_SCL") (class "Default")
      (node (ref "A2") (pin "8") (pinfunction "SCL_8") (pintype "bidirectional"))
      (node (ref "J5") (pin "3") (pinfunction "3_3") (pintype "bidirectional"))
    )
    (net (code "18") (name "CAMERA-2_SDA") (class "Default")
      (node (ref "A2") (pin "7") (pinfunction "SDA_7") (pintype "bidirectional"))
      (node (ref "J5") (pin "5") (pinfunction "5_5") (pintype "bidirectional"))
    )
    (net (code "19") (name "CAMERA_MISO") (class "Default")
      (node (ref "A1") (pin "3") (pinfunction "MISO_3") (pintype "bidirectional"))
      (node (ref "A2") (pin "3") (pinfunction "MISO_3") (pintype "bidirectional"))
      (node (ref "J5") (pin "8") (pinfunction "8_8") (pintype "bidirectional"))
    )
    (net (code "20") (name "CAMERA_MOSI") (class "Default")
      (node (ref "A1") (pin "2") (pinfunction "MOSI_2") (pintype "bidirectional"))
      (node (ref "A2") (pin "2") (pinfunction "MOSI_2") (pintype "bidirectional"))
      (node (ref "J5") (pin "10") (pinfunction "10_10") (pintype "bidirectional"))
    )
    (net (code "21") (name "CAMERA_SCLK") (class "Default")
      (node (ref "A1") (pin "4") (pinfunction "SCLK_4") (pintype "bidirectional"))
      (node (ref "A2") (pin "4") (pinfunction "SCLK_4") (pintype "bidirectional"))
      (node (ref "J5") (pin "9") (pinfunction "9_9") (pintype "bidirectional"))
    )
    (net (code "22") (name "CAM_5V_PRESENT") (class "Default")
      (node (ref "J5") (pin "1") (pinfunction "1_1") (pintype "bidirectional"))
      (node (ref "R2") (pin "1") (pinfunction "1_1") (pintype "passive"))
      (node (ref "R3") (pin "2") (pinfunction "2_2") (pintype "passive"))
    )
    (net (code "23") (name "GND") (class "Default")
      (node (ref "A1") (pin "5") (pinfunction "GND_5") (pintype "bidirectional"))
      (node (ref "A1") (pin "P$1") (pinfunction "MTG_1_P$1") (pintype "bidirectional"))
      (node (ref "A1") (pin "P$2") (pinfunction "MTG_2_P$2") (pintype "bidirectional"))
      (node (ref "A2") (pin "5") (pinfunction "GND_5") (pintype "bidirectional"))
      (node (ref "A2") (pin "P$1") (pinfunction "MTG_1_P$1") (pintype "bidirectional"))
      (node (ref "A2") (pin "P$2") (pinfunction "MTG_2_P$2") (pintype "bidirectional"))
      (node (ref "C1") (pin "2") (pinfunction "2_2") (pintype "passive"))
      (node (ref "C10") (pin "1") (pinfunction "1_1") (pintype "passive"))
      (node (ref "C11") (pin "2") (pinfunction "2_2") (pintype "passive"))
      (node (ref "C12") (pin "2") (pinfunction "2_2") (pintype "passive"))
      (node (ref "C13") (pin "2") (pinfunction "2_2") (pintype "passive"))
      (node (ref "C14") (pin "2") (pinfunction "2_2") (pintype "passive"))
      (node (ref "C15") (pin "2") (pinfunction "2_2") (pintype "passive"))
      (node (ref "C16") (pin "2") (pinfunction "2_2") (pintype "passive"))
      (node (ref "C19") (pin "2") (pinfunction "2_2") (pintype "passive"))
      (node (ref "C2") (pin "-") (pinfunction "-_-") (pintype "passive"))
      (node (ref "C20") (pin "2") (pinfunction "2_2") (pintype "passive"))
      (node (ref "C22") (pin "2") (pinfunction "2_2") (pintype "passive"))
      (node (ref "C24") (pin "1") (pinfunction "1_1") (pintype "passive"))
      (node (ref "C25") (pin "1") (pinfunction "1_1") (pintype "passive"))
      (node (ref "C26") (pin "1") (pinfunction "1_1") (pintype "passive"))
      (node (ref "C27") (pin "1") (pinfunction "1_1") (pintype "passive"))
      (node (ref "C28") (pin "1") (pinfunction "1_1") (pintype "passive"))
      (node (ref "C29") (pin "2") (pinfunction "2_2") (pintype "passive"))
      (node (ref "C3") (pin "1") (pinfunction "1_1") (pintype "passive"))
      (node (ref "C32") (pin "2") (pinfunction "2_2") (pintype "passive"))
      (node (ref "C33") (pin "2") (pinfunction "2_2") (pintype "passive"))
      (node (ref "C4") (pin "1") (pinfunction "1_1") (pintype "passive"))
      (node (ref "C5") (pin "1") (pinfunction "1_1") (pintype "passive"))
      (node (ref "C6") (pin "1") (pinfunction "1_1") (pintype "passive"))
      (node (ref "C7") (pin "2") (pinfunction "2_2") (pintype "passive"))
      (node (ref "C8") (pin "2") (pinfunction "2_2") (pintype "passive"))
      (node (ref "C9") (pin "2") (pinfunction "2_2") (pintype "passive"))
      (node (ref "H1") (pin "B3,2") (pinfunction "MOUNT_B3,2") (pintype "passive"))
      (node (ref "H2") (pin "B3,2") (pinfunction "MOUNT_B3,2") (pintype "passive"))
      (node (ref "H3") (pin "B3,2") (pinfunction "MOUNT_B3,2") (pintype "passive"))
      (node (ref "H4") (pin "B3,2") (pinfunction "MOUNT_B3,2") (pintype "passive"))
      (node (ref "J1") (pin "1") (pinfunction "GND_1") (pintype "bidirectional"))
      (node (ref "J6") (pin "3") (pinfunction "3_3") (pintype "passive"))
      (node (ref "J7") (pin "3") (pinfunction "3_3") (pintype "passive"))
      (node (ref "J8") (pin "1") (pinfunction "1_1") (pintype "passive"))
      (node (ref "Q1") (pin "2") (pinfunction "S_2") (pintype "passive"))
      (node (ref "R11") (pin "2") (pinfunction "2_2") (pintype "passive"))
      (node (ref "R18") (pin "2") (pinfunction "2_2") (pintype "passive"))
      (node (ref "R19") (pin "1") (pinfunction "1_1") (pintype "passive"))
      (node (ref "R25") (pin "2") (pinfunction "2_2") (pintype "passive"))
      (node (ref "R3") (pin "1") (pinfunction "1_1") (pintype "passive"))
      (node (ref "R33") (pin "1") (pinfunction "1_1") (pintype "passive"))
      (node (ref "R34") (pin "1") (pinfunction "1_1") (pintype "passive"))
      (node (ref "R35") (pin "1") (pinfunction "1_1") (pintype "passive"))
      (node (ref "R36") (pin "1") (pinfunction "1_1") (pintype "passive"))
      (node (ref "R38") (pin "1") (pinfunction "1_1") (pintype "passive"))
      (node (ref "R39") (pin "1") (pinfunction "1_1") (pintype "passive"))
      (node (ref "R42") (pin "2") (pinfunction "2_2") (pintype "passive"))
      (node (ref "R43") (pin "2") (pinfunction "2_2") (pintype "passive"))
      (node (ref "R45") (pin "2") (pinfunction "2_2") (pintype "passive"))
      (node (ref "R46") (pin "2") (pinfunction "2_2") (pintype "passive"))
      (node (ref "R47") (pin "2") (pinfunction "2_2") (pintype "passive"))
      (node (ref "R48") (pin "1") (pinfunction "1_1") (pintype "passive"))
      (node (ref "R49") (pin "1") (pinfunction "1_1") (pintype "passive"))
      (node (ref "R5") (pin "1") (pinfunction "1_1") (pintype "passive"))
      (node (ref "R50") (pin "1") (pinfunction "1_1") (pintype "passive"))
      (node (ref "R51") (pin "1") (pinfunction "1_1") (pintype "passive"))
      (node (ref "R52") (pin "1") (pinfunction "1_1") (pintype "passive"))
      (node (ref "R53") (pin "1") (pinfunction "1_1") (pintype "passive"))
      (node (ref "R54") (pin "1") (pinfunction "1_1") (pintype "passive"))
      (node (ref "R55") (pin "1") (pinfunction "1_1") (pintype "passive"))
      (node (ref "R57") (pin "2") (pinfunction "2_2") (pintype "passive"))
      (node (ref "R58") (pin "2") (pinfunction "2_2") (pintype "passive"))
      (node (ref "R6") (pin "1") (pinfunction "1_1") (pintype "passive"))
      (node (ref "S1") (pin "3") (pinfunction "P_3") (pintype "passive"))
      (node (ref "S1") (pin "4") (pinfunction "P1_4") (pintype "passive"))
      (node (ref "U1") (pin "14") (pinfunction "AVSS1_14") (pintype "bidirectional"))
      (node (ref "U1") (pin "19") (pinfunction "DVSS1_19") (pintype "bidirectional"))
      (node (ref "U1") (pin "49") (pinfunction "DVSS2_49") (pintype "bidirectional"))
      (node (ref "U1") (pin "61") (pinfunction "VSSU_61") (pintype "bidirectional"))
      (node (ref "U1") (pin "65") (pinfunction "VBUS_65") (pintype "bidirectional"))
      (node (ref "U1") (pin "68") (pinfunction "AVSS2_68") (pintype "bidirectional"))
      (node (ref "U10") (pin "2") (pinfunction "VSS_2") (pintype "power_in"))
      (node (ref "U2") (pin "2") (pinfunction "VSS_2") (pintype "power_in"))
      (node (ref "U3") (pin "10") (pinfunction "GND_10") (pintype "power_in"))
      (node (ref "U3") (pin "11") (pinfunction "MODE_11") (pintype "passive"))
      (node (ref "U3") (pin "6") (pinfunction "COM_6") (pintype "input"))
      (node (ref "U4") (pin "2") (pinfunction "VSS_2") (pintype "power_in"))
      (node (ref "U5") (pin "1") (pinfunction "S1_1") (pintype "passive"))
      (node (ref "U6") (pin "10") (pinfunction "PIN10(GND)_10") (pintype "bidirectional"))
      (node (ref "U6") (pin "15") (pinfunction "PIN15(GND)_15") (pintype "bidirectional"))
      (node (ref "U6") (pin "16") (pinfunction "PIN16(GND)_16") (pintype "bidirectional"))
      (node (ref "U6") (pin "17") (pinfunction "COM3/I2C_ADDR_17") (pintype "bidirectional"))
      (node (ref "U6") (pin "18") (pinfunction "COM2(GND)_18") (pintype "bidirectional"))
      (node (ref "U6") (pin "2") (pinfunction "GND_2") (pintype "power_in"))
      (node (ref "U6") (pin "25") (pinfunction "GND_25") (pintype "power_in"))
      (node (ref "U6") (pin "5") (pinfunction "PS1_5") (pintype "input"))
      (node (ref "U6") (pin "6") (pinfunction "PS0_6") (pintype "input"))
      (node (ref "U7") (pin "11") (pinfunction "GND(A)_11") (pintype "bidirectional"))
      (node (ref "U7") (pin "14") (pinfunction "GND(C)_14") (pintype "bidirectional"))
      (node (ref "U7") (pin "15") (pinfunction "OFF+(A,B,C)_15") (pintype "bidirectional"))
      (node (ref "U7") (pin "5") (pinfunction "GND(B)_5") (pintype "bidirectional"))
      (node (ref "U7") (pin "8") (pinfunction "S/R-(A,B,C)_8") (pintype "bidirectional"))
      (node (ref "U9") (pin "1") (pinfunction "SDO_1") (pintype "bidirectional"))
      (node (ref "U9") (pin "12") (pinfunction "CSB_12") (pintype "bidirectional"))
      (node (ref "U9") (pin "2") (pinfunction "GND_1_2") (pintype "bidirectional"))
      (node (ref "U9") (pin "3") (pinfunction "GND_2_3") (pintype "bidirectional"))
      (node (ref "U9") (pin "6") (pinfunction "GNDIO_6") (pintype "bidirectional"))
      (node (ref "U9") (pin "7") (pinfunction "GND_3_7") (pintype "bidirectional"))
      (node (ref "Y1") (pin "P3") (pinfunction "GND_P3") (pintype "power_in"))
      (node (ref "Y2") (pin "2") (pinfunction "2_2") (pintype "passive"))
      (node (ref "Y3") (pin "P3") (pinfunction "GND_P3") (pintype "power_in"))
    )
    (net (code "24") (name "HMC1053_RESET") (class "Default")
      (node (ref "TP1") (pin "1") (pinfunction "TP_1") (pintype "input"))
      (node (ref "U1") (pin "2") (pinfunction "P6.5/CB5/A5_2") (pintype "bidirectional"))
      (node (ref "U5") (pin "2") (pinfunction "G1_2") (pintype "passive"))
      (node (ref "U5") (pin "4") (pinfunction "G2_4") (pintype "passive"))
    )
    (net (code "25") (name "MAG_X_FIN") (class "Default")
      (node (ref "JP2A") (pin "8") (pinfunction "8_8") (pintype "passive"))
      (node (ref "U1") (pin "24") (pinfunction "P1.3/TA0.2_24") (pintype "bidirectional"))
    )
    (net (code "26") (name "MAG_X_RIN") (class "Default")
      (node (ref "JP2A") (pin "6") (pinfunction "6_6") (pintype "passive"))
      (node (ref "U1") (pin "23") (pinfunction "P1.2/TA0.1_23") (pintype "bidirectional"))
    )
    (net (code "27") (name "MAG_Y_FIN") (class "Default")
      (node (ref "JP2A") (pin "12") (pinfunction "12_12") (pintype "passive"))
      (node (ref "U1") (pin "26") (pinfunction "P1.5/TA0.4_26") (pintype "bidirectional"))
    )
    (net (code "28") (name "MAG_Y_RIN") (class "Default")
      (node (ref "JP2A") (pin "10") (pinfunction "10_10") (pintype "passive"))
      (node (ref "U1") (pin "25") (pinfunction "P1.4/TA0.3_25") (pintype "bidirectional"))
    )
    (net (code "29") (name "MAG_Z_FIN") (class "Default")
      (node (ref "JP2B") (pin "4") (pinfunction "4_4") (pintype "passive"))
      (node (ref "U1") (pin "30") (pinfunction "P2.1/TA1.2_30") (pintype "bidirectional"))
    )
    (net (code "30") (name "MAG_Z_RIN") (class "Default")
      (node (ref "JP2B") (pin "2") (pinfunction "2_2") (pintype "passive"))
      (node (ref "U1") (pin "29") (pinfunction "P2.0/TA1.1_29") (pintype "bidirectional"))
    )
    (net (code "31") (name "MSP430_ACTIVE") (class "Default")
      (node (ref "U1") (pin "1") (pinfunction "P6.4/CB4/A4_1") (pintype "bidirectional"))
    )
    (net (code "32") (name "MSP_OBC_RESET") (class "Default")
      (node (ref "J3") (pin "5") (pinfunction "5_5") (pintype "passive"))
      (node (ref "Q1") (pin "1") (pinfunction "G_1") (pintype "passive"))
      (node (ref "R36") (pin "2") (pinfunction "2_2") (pintype "passive"))
    )
    (net (code "33") (name "Net-(J1-5V)") (class "Default")
      (node (ref "J1") (pin "2") (pinfunction "5V_2") (pintype "bidirectional"))
      (node (ref "R42") (pin "1") (pinfunction "1_1") (pintype "passive"))
    )
    (net (code "34") (name "Net-(J1-NC)") (class "Default")
      (node (ref "J1") (pin "10") (pinfunction "NC_10") (pintype "bidirectional"))
      (node (ref "R43") (pin "1") (pinfunction "1_1") (pintype "passive"))
    )
    (net (code "35") (name "Net-(JP1-Pad6)") (class "Default")
      (node (ref "JP1") (pin "6") (pinfunction "6_6") (pintype "passive"))
      (node (ref "R45") (pin "1") (pinfunction "1_1") (pintype "passive"))
    )
    (net (code "36") (name "Net-(JP2A-Pad4)") (class "Default")
      (node (ref "JP2A") (pin "4") (pinfunction "4_4") (pintype "passive"))
      (node (ref "R55") (pin "2") (pinfunction "2_2") (pintype "passive"))
    )
    (net (code "37") (name "Net-(R10-Pad2)") (class "Default")
      (node (ref "R10") (pin "2") (pinfunction "2_2") (pintype "passive"))
      (node (ref "R11") (pin "1") (pinfunction "1_1") (pintype "passive"))
      (node (ref "R14") (pin "1") (pinfunction "1_1") (pintype "passive"))
    )
    (net (code "38") (name "Net-(R17-Pad2)") (class "Default")
      (node (ref "R17") (pin "2") (pinfunction "2_2") (pintype "passive"))
      (node (ref "R18") (pin "1") (pinfunction "1_1") (pintype "passive"))
      (node (ref "R22") (pin "1") (pinfunction "1_1") (pintype "passive"))
    )
    (net (code "39") (name "Net-(R24-Pad2)") (class "Default")
      (node (ref "R24") (pin "2") (pinfunction "2_2") (pintype "passive"))
      (node (ref "R25") (pin "1") (pinfunction "1_1") (pintype "passive"))
      (node (ref "R28") (pin "1") (pinfunction "1_1") (pintype "passive"))
    )
    (net (code "40") (name "Net-(TP5-TP)") (class "Default")
      (node (ref "R33") (pin "2") (pinfunction "2_2") (pintype "passive"))
      (node (ref "TP5") (pin "1") (pinfunction "TP_1") (pintype "input"))
      (node (ref "U3") (pin "2") (pinfunction "CH0_2") (pintype "input"))
    )
    (net (code "41") (name "Net-(TP6-TP)") (class "Default")
      (node (ref "C18") (pin "1") (pinfunction "1_1") (pintype "passive"))
      (node (ref "TP6") (pin "1") (pinfunction "TP_1") (pintype "input"))
      (node (ref "U5") (pin "5") (pinfunction "D2_2_5") (pintype "passive"))
    )
    (net (code "42") (name "Net-(TP7-TP)") (class "Default")
      (node (ref "R16") (pin "2") (pinfunction "2_2") (pintype "passive"))
      (node (ref "TP7") (pin "1") (pinfunction "TP_1") (pintype "input"))
      (node (ref "U7") (pin "3") (pinfunction "S/R+(A,B)_3") (pintype "bidirectional"))
      (node (ref "U7") (pin "6") (pinfunction "S/R+(C)_6") (pintype "bidirectional"))
    )
    (net (code "43") (name "Net-(TP8-TP)") (class "Default")
      (node (ref "C18") (pin "2") (pinfunction "2_2") (pintype "passive"))
      (node (ref "R16") (pin "1") (pinfunction "1_1") (pintype "passive"))
      (node (ref "TP8") (pin "1") (pinfunction "TP_1") (pintype "input"))
    )
    (net (code "44") (name "Net-(U1-AVCC1)") (class "Default")
      (node (ref "C1") (pin "1") (pinfunction "1_1") (pintype "passive"))
      (node (ref "R1") (pin "1") (pinfunction "1_1") (pintype "passive"))
      (node (ref "U1") (pin "11") (pinfunction "AVCC1_11") (pintype "bidirectional"))
    )
    (net (code "45") (name "Net-(U1-P5.2{slash}XT2IN)") (class "Default")
      (node (ref "U1") (pin "69") (pinfunction "P5.2/XT2IN_69") (pintype "bidirectional"))
      (node (ref "Y2") (pin "3") (pinfunction "3_3") (pintype "passive"))
    )
    (net (code "46") (name "Net-(U1-P5.3{slash}XT2OUT)") (class "Default")
      (node (ref "U1") (pin "70") (pinfunction "P5.3/XT2OUT_70") (pintype "bidirectional"))
      (node (ref "Y2") (pin "1") (pinfunction "1_1") (pintype "passive"))
    )
    (net (code "47") (name "Net-(U1-P5.4{slash}XIN)") (class "Default")
      (node (ref "C3") (pin "2") (pinfunction "2_2") (pintype "passive"))
      (node (ref "U1") (pin "12") (pinfunction "P5.4/XIN_12") (pintype "bidirectional"))
      (node (ref "Y1") (pin "P2") (pinfunction "2_P2") (pintype "bidirectional"))
    )
    (net (code "48") (name "Net-(U1-P5.5{slash}XOUT)") (class "Default")
      (node (ref "C4") (pin "2") (pinfunction "2_2") (pintype "passive"))
      (node (ref "U1") (pin "13") (pinfunction "P5.5/XOUT_13") (pintype "bidirectional"))
      (node (ref "Y1") (pin "P1") (pinfunction "1_P1") (pintype "bidirectional"))
    )
    (net (code "49") (name "Net-(U1-PUR)") (class "Default")
      (node (ref "R6") (pin "2") (pinfunction "2_2") (pintype "passive"))
      (node (ref "U1") (pin "63") (pinfunction "PUR_63") (pintype "bidirectional"))
    )
    (net (code "50") (name "Net-(U1-V1.8)") (class "Default")
      (node (ref "R46") (pin "1") (pinfunction "1_1") (pintype "passive"))
      (node (ref "U1") (pin "67") (pinfunction "V1.8_67") (pintype "bidirectional"))
    )
    (net (code "51") (name "Net-(U1-VCORE)") (class "Default")
      (node (ref "C6") (pin "2") (pinfunction "2_2") (pintype "passive"))
      (node (ref "U1") (pin "20") (pinfunction "VCORE_20") (pintype "bidirectional"))
    )
    (net (code "52") (name "Net-(U1-VUSB)") (class "Default")
      (node (ref "R47") (pin "1") (pinfunction "1_1") (pintype "passive"))
      (node (ref "U1") (pin "66") (pinfunction "VUSB_66") (pintype "bidirectional"))
    )
    (net (code "53") (name "Net-(U2-IN+)") (class "Default")
      (node (ref "R20") (pin "1") (pinfunction "1_1") (pintype "passive"))
      (node (ref "R22") (pin "2") (pinfunction "2_2") (pintype "passive"))
      (node (ref "U2") (pin "3") (pinfunction "IN+_3") (pintype "input"))
    )
    (net (code "54") (name "Net-(U2-IN-)") (class "Default")
      (node (ref "C21") (pin "1") (pinfunction "1_1") (pintype "passive"))
      (node (ref "R21") (pin "1") (pinfunction "1_1") (pintype "passive"))
      (node (ref "R23") (pin "2") (pinfunction "2_2") (pintype "passive"))
      (node (ref "U2") (pin "4") (pinfunction "IN-_4") (pintype "input"))
    )
    (net (code "55") (name "Net-(U3-BUSY)") (class "Default")
      (node (ref "R38") (pin "2") (pinfunction "2_2") (pintype "passive"))
      (node (ref "U3") (pin "13") (pinfunction "BUSY_13") (pintype "output"))
    )
    (net (code "56") (name "Net-(U3-~{SHDN})") (class "Default")
      (node (ref "C29") (pin "1") (pinfunction "1_1") (pintype "passive"))
      (node (ref "R37") (pin "2") (pinfunction "2_2") (pintype "passive"))
      (node (ref "U3") (pin "7") (pinfunction "~{SHDN}_7") (pintype "passive"))
    )
    (net (code "57") (name "Net-(U4-IN+)") (class "Default")
      (node (ref "R26") (pin "1") (pinfunction "1_1") (pintype "passive"))
      (node (ref "R28") (pin "2") (pinfunction "2_2") (pintype "passive"))
      (node (ref "U4") (pin "3") (pinfunction "IN+_3") (pintype "input"))
    )
    (net (code "58") (name "Net-(U4-IN-)") (class "Default")
      (node (ref "C23") (pin "1") (pinfunction "1_1") (pintype "passive"))
      (node (ref "R27") (pin "1") (pinfunction "1_1") (pintype "passive"))
      (node (ref "R29") (pin "2") (pinfunction "2_2") (pintype "passive"))
      (node (ref "U4") (pin "4") (pinfunction "IN-_4") (pintype "input"))
    )
    (net (code "59") (name "Net-(U5-D1_2)") (class "Default")
      (node (ref "U5") (pin "6") (pinfunction "D2_1_6") (pintype "passive"))
      (node (ref "U5") (pin "7") (pinfunction "D1_2_7") (pintype "passive"))
    )
    (net (code "60") (name "Net-(U5-S2)") (class "Default")
      (node (ref "C10") (pin "2") (pinfunction "2_2") (pintype "passive"))
      (node (ref "R9") (pin "1") (pinfunction "1_1") (pintype "passive"))
      (node (ref "U5") (pin "3") (pinfunction "S2_3") (pintype "passive"))
    )
    (net (code "61") (name "Net-(U6-CAP)") (class "Default")
      (node (ref "C24") (pin "2") (pinfunction "2_2") (pintype "passive"))
      (node (ref "U6") (pin "9") (pinfunction "CAP_9") (pintype "passive"))
    )
    (net (code "62") (name "Net-(U6-NC_1)") (class "Default")
      (node (ref "R48") (pin "2") (pinfunction "2_2") (pintype "passive"))
      (node (ref "U6") (pin "1") (pinfunction "NC_1_1") (pintype "bidirectional"))
    )
    (net (code "63") (name "Net-(U6-NC_2)") (class "Default")
      (node (ref "R49") (pin "2") (pinfunction "2_2") (pintype "passive"))
      (node (ref "U6") (pin "12") (pinfunction "NC_2_12") (pintype "bidirectional"))
    )
    (net (code "64") (name "Net-(U6-NC_3)") (class "Default")
      (node (ref "R50") (pin "2") (pinfunction "2_2") (pintype "passive"))
      (node (ref "U6") (pin "13") (pinfunction "NC_3_13") (pintype "bidirectional"))
    )
    (net (code "65") (name "Net-(U6-NC_4)") (class "Default")
      (node (ref "R51") (pin "2") (pinfunction "2_2") (pintype "passive"))
      (node (ref "U6") (pin "21") (pinfunction "NC_4_21") (pintype "bidirectional"))
    )
    (net (code "66") (name "Net-(U6-NC_5)") (class "Default")
      (node (ref "R52") (pin "2") (pinfunction "2_2") (pintype "passive"))
      (node (ref "U6") (pin "22") (pinfunction "NC_5_22") (pintype "bidirectional"))
    )
    (net (code "67") (name "Net-(U6-NC_6)") (class "Default")
      (node (ref "R53") (pin "2") (pinfunction "2_2") (pintype "passive"))
      (node (ref "U6") (pin "23") (pinfunction "NC_6_23") (pintype "bidirectional"))
    )
    (net (code "68") (name "Net-(U6-NC_7)") (class "Default")
      (node (ref "R54") (pin "2") (pinfunction "2_2") (pintype "passive"))
      (node (ref "U6") (pin "24") (pinfunction "NC_7_24") (pintype "bidirectional"))
    )
    (net (code "69") (name "Net-(U6-PIN7(SWDIO))") (class "Default")
      (node (ref "J2") (pin "1") (pinfunction "1_1") (pintype "passive"))
      (node (ref "R35") (pin "2") (pinfunction "2_2") (pintype "passive"))
      (node (ref "U6") (pin "7") (pinfunction "PIN7(SWDIO)_7") (pintype "bidirectional"))
    )
    (net (code "70") (name "Net-(U6-PIN8(SWCLK))") (class "Default")
      (node (ref "J2") (pin "2") (pinfunction "2_2") (pintype "passive"))
      (node (ref "R39") (pin "2") (pinfunction "2_2") (pintype "passive"))
      (node (ref "U6") (pin "8") (pinfunction "PIN8(SWCLK)_8") (pintype "bidirectional"))
    )
    (net (code "71") (name "Net-(U6-XIN32)") (class "Default")
      (node (ref "C26") (pin "2") (pinfunction "2_2") (pintype "passive"))
      (node (ref "U6") (pin "27") (pinfunction "XIN32_27") (pintype "input"))
      (node (ref "Y3") (pin "P1") (pinfunction "1_P1") (pintype "bidirectional"))
    )
    (net (code "72") (name "Net-(U6-XOUT32)") (class "Default")
      (node (ref "C27") (pin "2") (pinfunction "2_2") (pintype "passive"))
      (node (ref "U6") (pin "26") (pinfunction "XOUT32_26") (pintype "output"))
      (node (ref "Y3") (pin "P2") (pinfunction "2_P2") (pintype "bidirectional"))
    )
    (net (code "73") (name "Net-(U6-~{BOOT_LOAD_PIN})") (class "Default")
      (node (ref "R30") (pin "1") (pinfunction "1_1") (pintype "passive"))
      (node (ref "U6") (pin "4") (pinfunction "~{BOOT_LOAD_PIN}_4") (pintype "bidirectional"))
    )
    (net (code "74") (name "Net-(U7-OFF-(A,B))") (class "Default")
      (node (ref "R19") (pin "2") (pinfunction "2_2") (pintype "passive"))
      (node (ref "U7") (pin "2") (pinfunction "OFF-(A,B)_2") (pintype "bidirectional"))
      (node (ref "U7") (pin "7") (pinfunction "OFF-(C)_7") (pintype "bidirectional"))
    )
    (net (code "75") (name "Net-(U9-DNC_1)") (class "Default")
      (node (ref "R57") (pin "1") (pinfunction "1_1") (pintype "passive"))
      (node (ref "U9") (pin "10") (pinfunction "DNC_1_10") (pintype "bidirectional"))
    )
    (net (code "76") (name "Net-(U9-DNC_2)") (class "Default")
      (node (ref "R58") (pin "1") (pinfunction "1_1") (pintype "passive"))
      (node (ref "U9") (pin "11") (pinfunction "DNC_2_11") (pintype "bidirectional"))
    )
    (net (code "77") (name "Net-(U10-IN+)") (class "Default")
      (node (ref "R12") (pin "1") (pinfunction "1_1") (pintype "passive"))
      (node (ref "R14") (pin "2") (pinfunction "2_2") (pintype "passive"))
      (node (ref "U10") (pin "3") (pinfunction "IN+_3") (pintype "input"))
    )
    (net (code "78") (name "Net-(U10-IN-)") (class "Default")
      (node (ref "C17") (pin "1") (pinfunction "1_1") (pintype "passive"))
      (node (ref "R13") (pin "1") (pinfunction "1_1") (pintype "passive"))
      (node (ref "R15") (pin "2") (pinfunction "2_2") (pintype "passive"))
      (node (ref "U10") (pin "4") (pinfunction "IN-_4") (pintype "input"))
    )
    (net (code "79") (name "OUT_A_N") (class "Default")
      (node (ref "R12") (pin "2") (pinfunction "2_2") (pintype "passive"))
      (node (ref "TP13") (pin "1") (pinfunction "TP_1") (pintype "input"))
      (node (ref "U7") (pin "10") (pinfunction "OUT-(A)_10") (pintype "bidirectional"))
    )
    (net (code "80") (name "OUT_A_P") (class "Default")
      (node (ref "R13") (pin "2") (pinfunction "2_2") (pintype "passive"))
      (node (ref "TP12") (pin "1") (pinfunction "TP_1") (pintype "input"))
      (node (ref "U7") (pin "16") (pinfunction "OUT+(A)_16") (pintype "bidirectional"))
    )
    (net (code "81") (name "OUT_B_N") (class "Default")
      (node (ref "R20") (pin "2") (pinfunction "2_2") (pintype "passive"))
      (node (ref "TP15") (pin "1") (pinfunction "TP_1") (pintype "input"))
      (node (ref "U7") (pin "4") (pinfunction "OUT-(B)_4") (pintype "bidirectional"))
    )
    (net (code "82") (name "OUT_B_P") (class "Default")
      (node (ref "R21") (pin "2") (pinfunction "2_2") (pintype "passive"))
      (node (ref "TP14") (pin "1") (pinfunction "TP_1") (pintype "input"))
      (node (ref "U7") (pin "12") (pinfunction "OUT+(B)_12") (pintype "bidirectional"))
    )
    (net (code "83") (name "OUT_C_N") (class "Default")
      (node (ref "R26") (pin "2") (pinfunction "2_2") (pintype "passive"))
      (node (ref "TP17") (pin "1") (pinfunction "TP_1") (pintype "input"))
      (node (ref "U7") (pin "9") (pinfunction "OUT-(C)_9") (pintype "bidirectional"))
    )
    (net (code "84") (name "OUT_C_P") (class "Default")
      (node (ref "R27") (pin "2") (pinfunction "2_2") (pintype "passive"))
      (node (ref "TP16") (pin "1") (pinfunction "TP_1") (pintype "input"))
      (node (ref "U7") (pin "13") (pinfunction "OUT+(C)_13") (pintype "bidirectional"))
    )
    (net (code "85") (name "P1.7{slash}CTS") (class "Default")
      (node (ref "J1") (pin "5") (pinfunction "CTS_5") (pintype "bidirectional"))
      (node (ref "U1") (pin "28") (pinfunction "P1.7/TA1.0_28") (pintype "bidirectional"))
    )
    (net (code "86") (name "P4.4{slash}UCA1TXD") (class "Default")
      (node (ref "J1") (pin "7") (pinfunction "TXD_7") (pintype "bidirectional"))
      (node (ref "U1") (pin "51") (pinfunction "P4.4/PM_UCA1TXD/PM_UCA1SIMO_51") (pintype "bidirectional"))
    )
    (net (code "87") (name "P4.5{slash}UCA1RXD") (class "Default")
      (node (ref "J1") (pin "6") (pinfunction "RXD_6") (pintype "bidirectional"))
      (node (ref "U1") (pin "52") (pinfunction "P4.5/PM_UCA1RXD/PM_UCA1SOMI_52") (pintype "bidirectional"))
    )
    (net (code "88") (name "P6.7{slash}RTS") (class "Default")
      (node (ref "J1") (pin "4") (pinfunction "RTS_4") (pintype "bidirectional"))
      (node (ref "U1") (pin "4") (pinfunction "P6.7/CB7/A7_4") (pintype "bidirectional"))
    )
    (net (code "89") (name "RESERVED_1") (class "Default")
      (node (ref "J3") (pin "6") (pinfunction "6_6") (pintype "passive"))
      (node (ref "U1") (pin "35") (pinfunction "P2.6/RTCCLK/DMAE0_35") (pintype "bidirectional"))
    )
    (net (code "90") (name "RESERVED_2") (class "Default")
      (node (ref "J3") (pin "8") (pinfunction "8_8") (pintype "passive"))
      (node (ref "U1") (pin "36") (pinfunction "P2.7/UCB0STE/UCA0CLK_36") (pintype "bidirectional"))
    )
    (net (code "91") (name "RST{slash}SBWTDIO") (class "Default")
      (node (ref "C7") (pin "1") (pinfunction "1_1") (pintype "passive"))
      (node (ref "J1") (pin "8") (pinfunction "SBWTDIO_8") (pintype "bidirectional"))
      (node (ref "Q1") (pin "3") (pinfunction "D_3") (pintype "passive"))
      (node (ref "R7") (pin "1") (pinfunction "1_1") (pintype "passive"))
      (node (ref "S1") (pin "1") (pinfunction "S_1") (pintype "passive"))
      (node (ref "S1") (pin "2") (pinfunction "S1_2") (pintype "passive"))
      (node (ref "U1") (pin "76") (pinfunction "RST/NMI/SBWTDIO_76") (pintype "bidirectional"))
    )
    (net (code "92") (name "RW_X_DIR") (class "Default")
      (node (ref "JP2B") (pin "3") (pinfunction "3_3") (pintype "passive"))
      (node (ref "U1") (pin "53") (pinfunction "P4.6/PM_NONE_53") (pintype "bidirectional"))
    )
    (net (code "93") (name "RW_X_LOCK") (class "Default")
      (node (ref "JP2A") (pin "11") (pinfunction "11_11") (pintype "passive"))
      (node (ref "U1") (pin "21") (pinfunction "P1.0/TA0CLK/ACLK_21") (pintype "bidirectional"))
    )
    (net (code "94") (name "RW_X_SPEED_CTRL") (class "Default")
      (node (ref "JP2A") (pin "9") (pinfunction "9_9") (pintype "passive"))
      (node (ref "U1") (pin "42") (pinfunction "P3.5/TB0.5_42") (pintype "bidirectional"))
    )
    (net (code "95") (name "RW_Y_DIR") (class "Default")
      (node (ref "JP2B") (pin "5") (pinfunction "5_5") (pintype "passive"))
      (node (ref "U1") (pin "54") (pinfunction "P4.7/PM_NONE_54") (pintype "bidirectional"))
    )
    (net (code "96") (name "RW_Y_LOCK") (class "Default")
      (node (ref "JP2B") (pin "9") (pinfunction "9_9") (pintype "passive"))
      (node (ref "U1") (pin "22") (pinfunction "P1.1/TA0.0_22") (pintype "bidirectional"))
    )
    (net (code "97") (name "RW_Y_SPEED_CTRL") (class "Default")
      (node (ref "JP2B") (pin "7") (pinfunction "7_7") (pintype "passive"))
      (node (ref "U1") (pin "33") (pinfunction "P2.4/TA2.1_33") (pintype "bidirectional"))
    )
    (net (code "98") (name "RW_Z_DIR") (class "Default")
      (node (ref "JP2A") (pin "3") (pinfunction "3_3") (pintype "passive"))
      (node (ref "U1") (pin "55") (pinfunction "P5.6/TB0.0_55") (pintype "bidirectional"))
    )
    (net (code "99") (name "RW_Z_LOCK") (class "Default")
      (node (ref "JP2A") (pin "7") (pinfunction "7_7") (pintype "passive"))
      (node (ref "U1") (pin "27") (pinfunction "P1.6/TA1CLK/CBOUT_27") (pintype "bidirectional"))
    )
    (net (code "100") (name "RW_Z_SPEED_CTRL") (class "Default")
      (node (ref "JP2A") (pin "5") (pinfunction "5_5") (pintype "passive"))
      (node (ref "U1") (pin "34") (pinfunction "P2.5/TA2.2_34") (pintype "bidirectional"))
    )
    (net (code "101") (name "TEST{slash}SBWTCK") (class "Default")
      (node (ref "J1") (pin "9") (pinfunction "SBWTCK_9") (pintype "bidirectional"))
      (node (ref "U1") (pin "71") (pinfunction "TEST/SBWTCK_71") (pintype "bidirectional"))
    )
    (net (code "102") (name "UCA0RXD") (class "Default")
      (node (ref "J3") (pin "1") (pinfunction "1_1") (pintype "passive"))
      (node (ref "J4") (pin "2") (pinfunction "2_2") (pintype "passive"))
      (node (ref "U1") (pin "41") (pinfunction "P3.4/UCA0RXD/UCA0SOMI_41") (pintype "bidirectional"))
    )
    (net (code "103") (name "UCA0TXD") (class "Default")
      (node (ref "J3") (pin "3") (pinfunction "3_3") (pintype "passive"))
      (node (ref "J4") (pin "1") (pinfunction "1_1") (pintype "passive"))
      (node (ref "U1") (pin "40") (pinfunction "P3.3/UCA0TXD/UCA0SIMO_40") (pintype "bidirectional"))
    )
    (net (code "104") (name "UCB0_SPI_CLK") (class "Default")
      (node (ref "J8") (pin "2") (pinfunction "2_2") (pintype "passive"))
      (node (ref "JP1") (pin "7") (pinfunction "7_7") (pintype "passive"))
      (node (ref "JP2B") (pin "6") (pinfunction "6_6") (pintype "passive"))
      (node (ref "U1") (pin "39") (pinfunction "P3.2/UCB0CLK/UCA0STE_39") (pintype "bidirectional"))
      (node (ref "U3") (pin "16") (pinfunction "DCLK_16") (pintype "input"))
    )
    (net (code "105") (name "UCB0_SPI_MISO") (class "Default")
      (node (ref "J8") (pin "5") (pinfunction "5_5") (pintype "passive"))
      (node (ref "JP1") (pin "11") (pinfunction "11_11") (pintype "passive"))
      (node (ref "JP2B") (pin "10") (pinfunction "10_10") (pintype "passive"))
      (node (ref "U1") (pin "38") (pinfunction "P3.1/UCB0SOMI/UCB0SCL_38") (pintype "bidirectional"))
      (node (ref "U3") (pin "12") (pinfunction "DOUT_12") (pintype "output"))
    )
    (net (code "106") (name "UCB0_SPI_MOSI") (class "Default")
      (node (ref "J8") (pin "4") (pinfunction "4_4") (pintype "passive"))
      (node (ref "JP1") (pin "9") (pinfunction "9_9") (pintype "passive"))
      (node (ref "JP2B") (pin "8") (pinfunction "8_8") (pintype "passive"))
      (node (ref "U1") (pin "37") (pinfunction "P3.0/UCB0SIMO/UCB0SDA_37") (pintype "bidirectional"))
      (node (ref "U3") (pin "14") (pinfunction "DIN_14") (pintype "input"))
    )
    (net (code "107") (name "UCB1_I2C_SCL") (class "Default")
      (node (ref "R60") (pin "1") (pinfunction "1_1") (pintype "passive"))
      (node (ref "TP18") (pin "1") (pinfunction "TP_1") (pintype "input"))
      (node (ref "U1") (pin "47") (pinfunction "P4.2/PM_UCB1SOMI/PM_UCB1SCL_47") (pintype "bidirectional"))
      (node (ref "U6") (pin "19") (pinfunction "COM1/SCL/RX_19") (pintype "bidirectional"))
      (node (ref "U9") (pin "13") (pinfunction "SCX_13") (pintype "bidirectional"))
    )
    (net (code "108") (name "UCB1_I2C_SDA") (class "Default")
      (node (ref "R59") (pin "1") (pinfunction "1_1") (pintype "passive"))
      (node (ref "TP19") (pin "1") (pinfunction "TP_1") (pintype "input"))
      (node (ref "U1") (pin "46") (pinfunction "P4.1/PM_UCB1SIMO/PM_UCB1SDA_46") (pintype "bidirectional"))
      (node (ref "U6") (pin "20") (pinfunction "COM0/SDA/TX_20") (pintype "bidirectional"))
      (node (ref "U9") (pin "14") (pinfunction "SDX_14") (pintype "bidirectional"))
    )
    (net (code "109") (name "Z-_SUN_3V_PRESENT") (class "Default")
      (node (ref "J3") (pin "9") (pinfunction "9_9") (pintype "passive"))
      (node (ref "JP1") (pin "4") (pinfunction "4_4") (pintype "passive"))
    )
    (net (code "110") (name "unconnected-(J3-Pad10)") (class "Default")
      (node (ref "J3") (pin "10") (pinfunction "10_10") (pintype "passive"))
    )
    (net (code "111") (name "unconnected-(J3-Pad11)") (class "Default")
      (node (ref "J3") (pin "11") (pinfunction "11_11") (pintype "passive"))
    )
    (net (code "112") (name "unconnected-(J3-Pad12)") (class "Default")
      (node (ref "J3") (pin "12") (pinfunction "12_12") (pintype "passive"))
    )
    (net (code "113") (name "unconnected-(JP1-Pad1)") (class "Default")
      (node (ref "JP1") (pin "1") (pinfunction "1_1") (pintype "passive"))
    )
    (net (code "114") (name "unconnected-(JP1-Pad2)") (class "Default")
      (node (ref "JP1") (pin "2") (pinfunction "2_2") (pintype "passive"))
    )
    (net (code "115") (name "unconnected-(MH1-MOUNT-Pad1)") (class "Default")
      (node (ref "MH1") (pin "1") (pinfunction "MOUNT_1") (pintype "no_connect"))
    )
    (net (code "116") (name "unconnected-(MH2-MOUNT-Pad1)") (class "Default")
      (node (ref "MH2") (pin "1") (pinfunction "MOUNT_1") (pintype "no_connect"))
    )
    (net (code "117") (name "unconnected-(MH3-MOUNT-Pad1)") (class "Default")
      (node (ref "MH3") (pin "1") (pinfunction "MOUNT_1") (pintype "no_connect"))
    )
    (net (code "118") (name "unconnected-(MH4-MOUNT-Pad1)") (class "Default")
      (node (ref "MH4") (pin "1") (pinfunction "MOUNT_1") (pintype "no_connect"))
    )
    (net (code "119") (name "unconnected-(U1-P3.7{slash}TB0OUTH{slash}SVMOUT-Pad44)") (class "Default")
      (node (ref "U1") (pin "44") (pinfunction "P3.7/TB0OUTH/SVMOUT_44") (pintype "bidirectional"))
    )
    (net (code "120") (name "unconnected-(U1-P4.0{slash}PM_UCB1STE{slash}PM_UCA1CLK-Pad45)") (class "Default")
      (node (ref "U1") (pin "45") (pinfunction "P4.0/PM_UCB1STE/PM_UCA1CLK_45") (pintype "bidirectional"))
    )
    (net (code "121") (name "unconnected-(U1-P4.3{slash}PM_UCB1CLK{slash}PM_UCA1STE-Pad48)") (class "Default")
      (node (ref "U1") (pin "48") (pinfunction "P4.3/PM_UCB1CLK/PM_UCA1STE_48") (pintype "bidirectional"))
    )
    (net (code "122") (name "unconnected-(U1-P5.0{slash}A8{slash}VREF+{slash}VEREF+-Pad9)") (class "Default")
      (node (ref "U1") (pin "9") (pinfunction "P5.0/A8/VREF+/VEREF+_9") (pintype "bidirectional"))
    )
    (net (code "123") (name "unconnected-(U1-P5.1{slash}A9{slash}VREF-{slash}VEREF--Pad10)") (class "Default")
      (node (ref "U1") (pin "10") (pinfunction "P5.1/A9/VREF-/VEREF-_10") (pintype "bidirectional"))
    )
    (net (code "124") (name "unconnected-(U1-P7.0{slash}CB8{slash}A12-Pad5)") (class "Default")
      (node (ref "U1") (pin "5") (pinfunction "P7.0/CB8/A12_5") (pintype "bidirectional"))
    )
    (net (code "125") (name "unconnected-(U1-P7.3{slash}CB11{slash}A15-Pad8)") (class "Default")
      (node (ref "U1") (pin "8") (pinfunction "P7.3/CB11/A15_8") (pintype "bidirectional"))
    )
    (net (code "126") (name "unconnected-(U1-P7.5{slash}TB0.3-Pad58)") (class "Default")
      (node (ref "U1") (pin "58") (pinfunction "P7.5/TB0.3_58") (pintype "bidirectional"))
    )
    (net (code "127") (name "unconnected-(U1-P7.6{slash}TB0.4-Pad59)") (class "Default")
      (node (ref "U1") (pin "59") (pinfunction "P7.6/TB0.4_59") (pintype "bidirectional"))
    )
    (net (code "128") (name "unconnected-(U1-P7.7{slash}TB0CLK{slash}MCLK-Pad60)") (class "Default")
      (node (ref "U1") (pin "60") (pinfunction "P7.7/TB0CLK/MCLK_60") (pintype "bidirectional"))
    )
    (net (code "129") (name "unconnected-(U1-P8.0-Pad15)") (class "Default")
      (node (ref "U1") (pin "15") (pinfunction "P8.0_15") (pintype "bidirectional"))
    )
    (net (code "130") (name "unconnected-(U1-P8.1-Pad16)") (class "Default")
      (node (ref "U1") (pin "16") (pinfunction "P8.1_16") (pintype "bidirectional"))
    )
    (net (code "131") (name "unconnected-(U1-P8.2-Pad17)") (class "Default")
      (node (ref "U1") (pin "17") (pinfunction "P8.2_17") (pintype "bidirectional"))
    )
    (net (code "132") (name "unconnected-(U1-PJ.0{slash}TDO-Pad72)") (class "Default")
      (node (ref "U1") (pin "72") (pinfunction "PJ.0/TDO_72") (pintype "bidirectional"))
    )
    (net (code "133") (name "unconnected-(U1-PJ.1{slash}TDI{slash}TCLK-Pad73)") (class "Default")
      (node (ref "U1") (pin "73") (pinfunction "PJ.1/TDI/TCLK_73") (pintype "bidirectional"))
    )
    (net (code "134") (name "unconnected-(U1-PJ.3{slash}TCK-Pad75)") (class "Default")
      (node (ref "U1") (pin "75") (pinfunction "PJ.3/TCK_75") (pintype "bidirectional"))
    )
    (net (code "135") (name "unconnected-(U1-PU.0{slash}DP-Pad62)") (class "Default")
      (node (ref "U1") (pin "62") (pinfunction "PU.0/DP_62") (pintype "bidirectional"))
    )
    (net (code "136") (name "unconnected-(U1-PU.1{slash}DM-Pad64)") (class "Default")
      (node (ref "U1") (pin "64") (pinfunction "PU.1/DM_64") (pintype "bidirectional"))
    )
    (net (code "137") (name "unconnected-(U5-D1_1-Pad8)") (class "Default")
      (node (ref "U5") (pin "8") (pinfunction "D1_1_8") (pintype "passive"))
    )
    (net (code "138") (name "~{CS}_CURR_SENSE_MTQR") (class "Default")
      (node (ref "JP2B") (pin "11") (pinfunction "11_11") (pintype "passive"))
      (node (ref "U1") (pin "56") (pinfunction "P5.7/TB0.1_56") (pintype "bidirectional"))
    )
    (net (code "139") (name "~{CS}_CURR_SENSE_RW") (class "Default")
      (node (ref "JP2B") (pin "1") (pinfunction "1_1") (pintype "passive"))
      (node (ref "U1") (pin "57") (pinfunction "P7.4/TB0.2_57") (pintype "bidirectional"))
    )
    (net (code "140") (name "~{CS}_HMC1053") (class "Default")
      (node (ref "TP2") (pin "1") (pinfunction "TP_1") (pintype "input"))
      (node (ref "U1") (pin "6") (pinfunction "P7.1/CB9/A13_6") (pintype "bidirectional"))
      (node (ref "U3") (pin "15") (pinfunction "~{CS}_15") (pintype "input"))
    )
    (net (code "141") (name "~{CS}_SPD_SENSE_RW") (class "Default")
      (node (ref "JP2B") (pin "12") (pinfunction "12_12") (pintype "passive"))
      (node (ref "U1") (pin "43") (pinfunction "P3.6/TB0.6_43") (pintype "bidirectional"))
    )
    (net (code "142") (name "~{CS}_SUN_X+") (class "Default")
      (node (ref "JP1") (pin "12") (pinfunction "12_12") (pintype "passive"))
      (node (ref "U1") (pin "74") (pinfunction "PJ.2/TMS_74") (pintype "bidirectional"))
    )
    (net (code "143") (name "~{CS}_SUN_X-") (class "Default")
      (node (ref "JP1") (pin "5") (pinfunction "5_5") (pintype "passive"))
      (node (ref "U1") (pin "77") (pinfunction "P6.0/CB0/A0_77") (pintype "bidirectional"))
    )
    (net (code "144") (name "~{CS}_SUN_Y+") (class "Default")
      (node (ref "JP1") (pin "10") (pinfunction "10_10") (pintype "passive"))
      (node (ref "U1") (pin "79") (pinfunction "P6.2/CB2/A2_79") (pintype "bidirectional"))
    )
    (net (code "145") (name "~{CS}_SUN_Y-") (class "Default")
      (node (ref "JP1") (pin "3") (pinfunction "3_3") (pintype "passive"))
      (node (ref "U1") (pin "80") (pinfunction "P6.3/CB3/A3_80") (pintype "bidirectional"))
    )
    (net (code "146") (name "~{CS}_SUN_Z+") (class "Default")
      (node (ref "J8") (pin "3") (pinfunction "3_3") (pintype "passive"))
      (node (ref "U1") (pin "78") (pinfunction "P6.1/CB1/A1_78") (pintype "bidirectional"))
    )
    (net (code "147") (name "~{CS}_SUN_Z-") (class "Default")
      (node (ref "JP1") (pin "8") (pinfunction "8_8") (pintype "passive"))
      (node (ref "U1") (pin "3") (pinfunction "P6.6/CB6/A6_3") (pintype "bidirectional"))
    )
  )
)
